# CPU.net
KiCad netlist of a schematic drawn in EAGLE
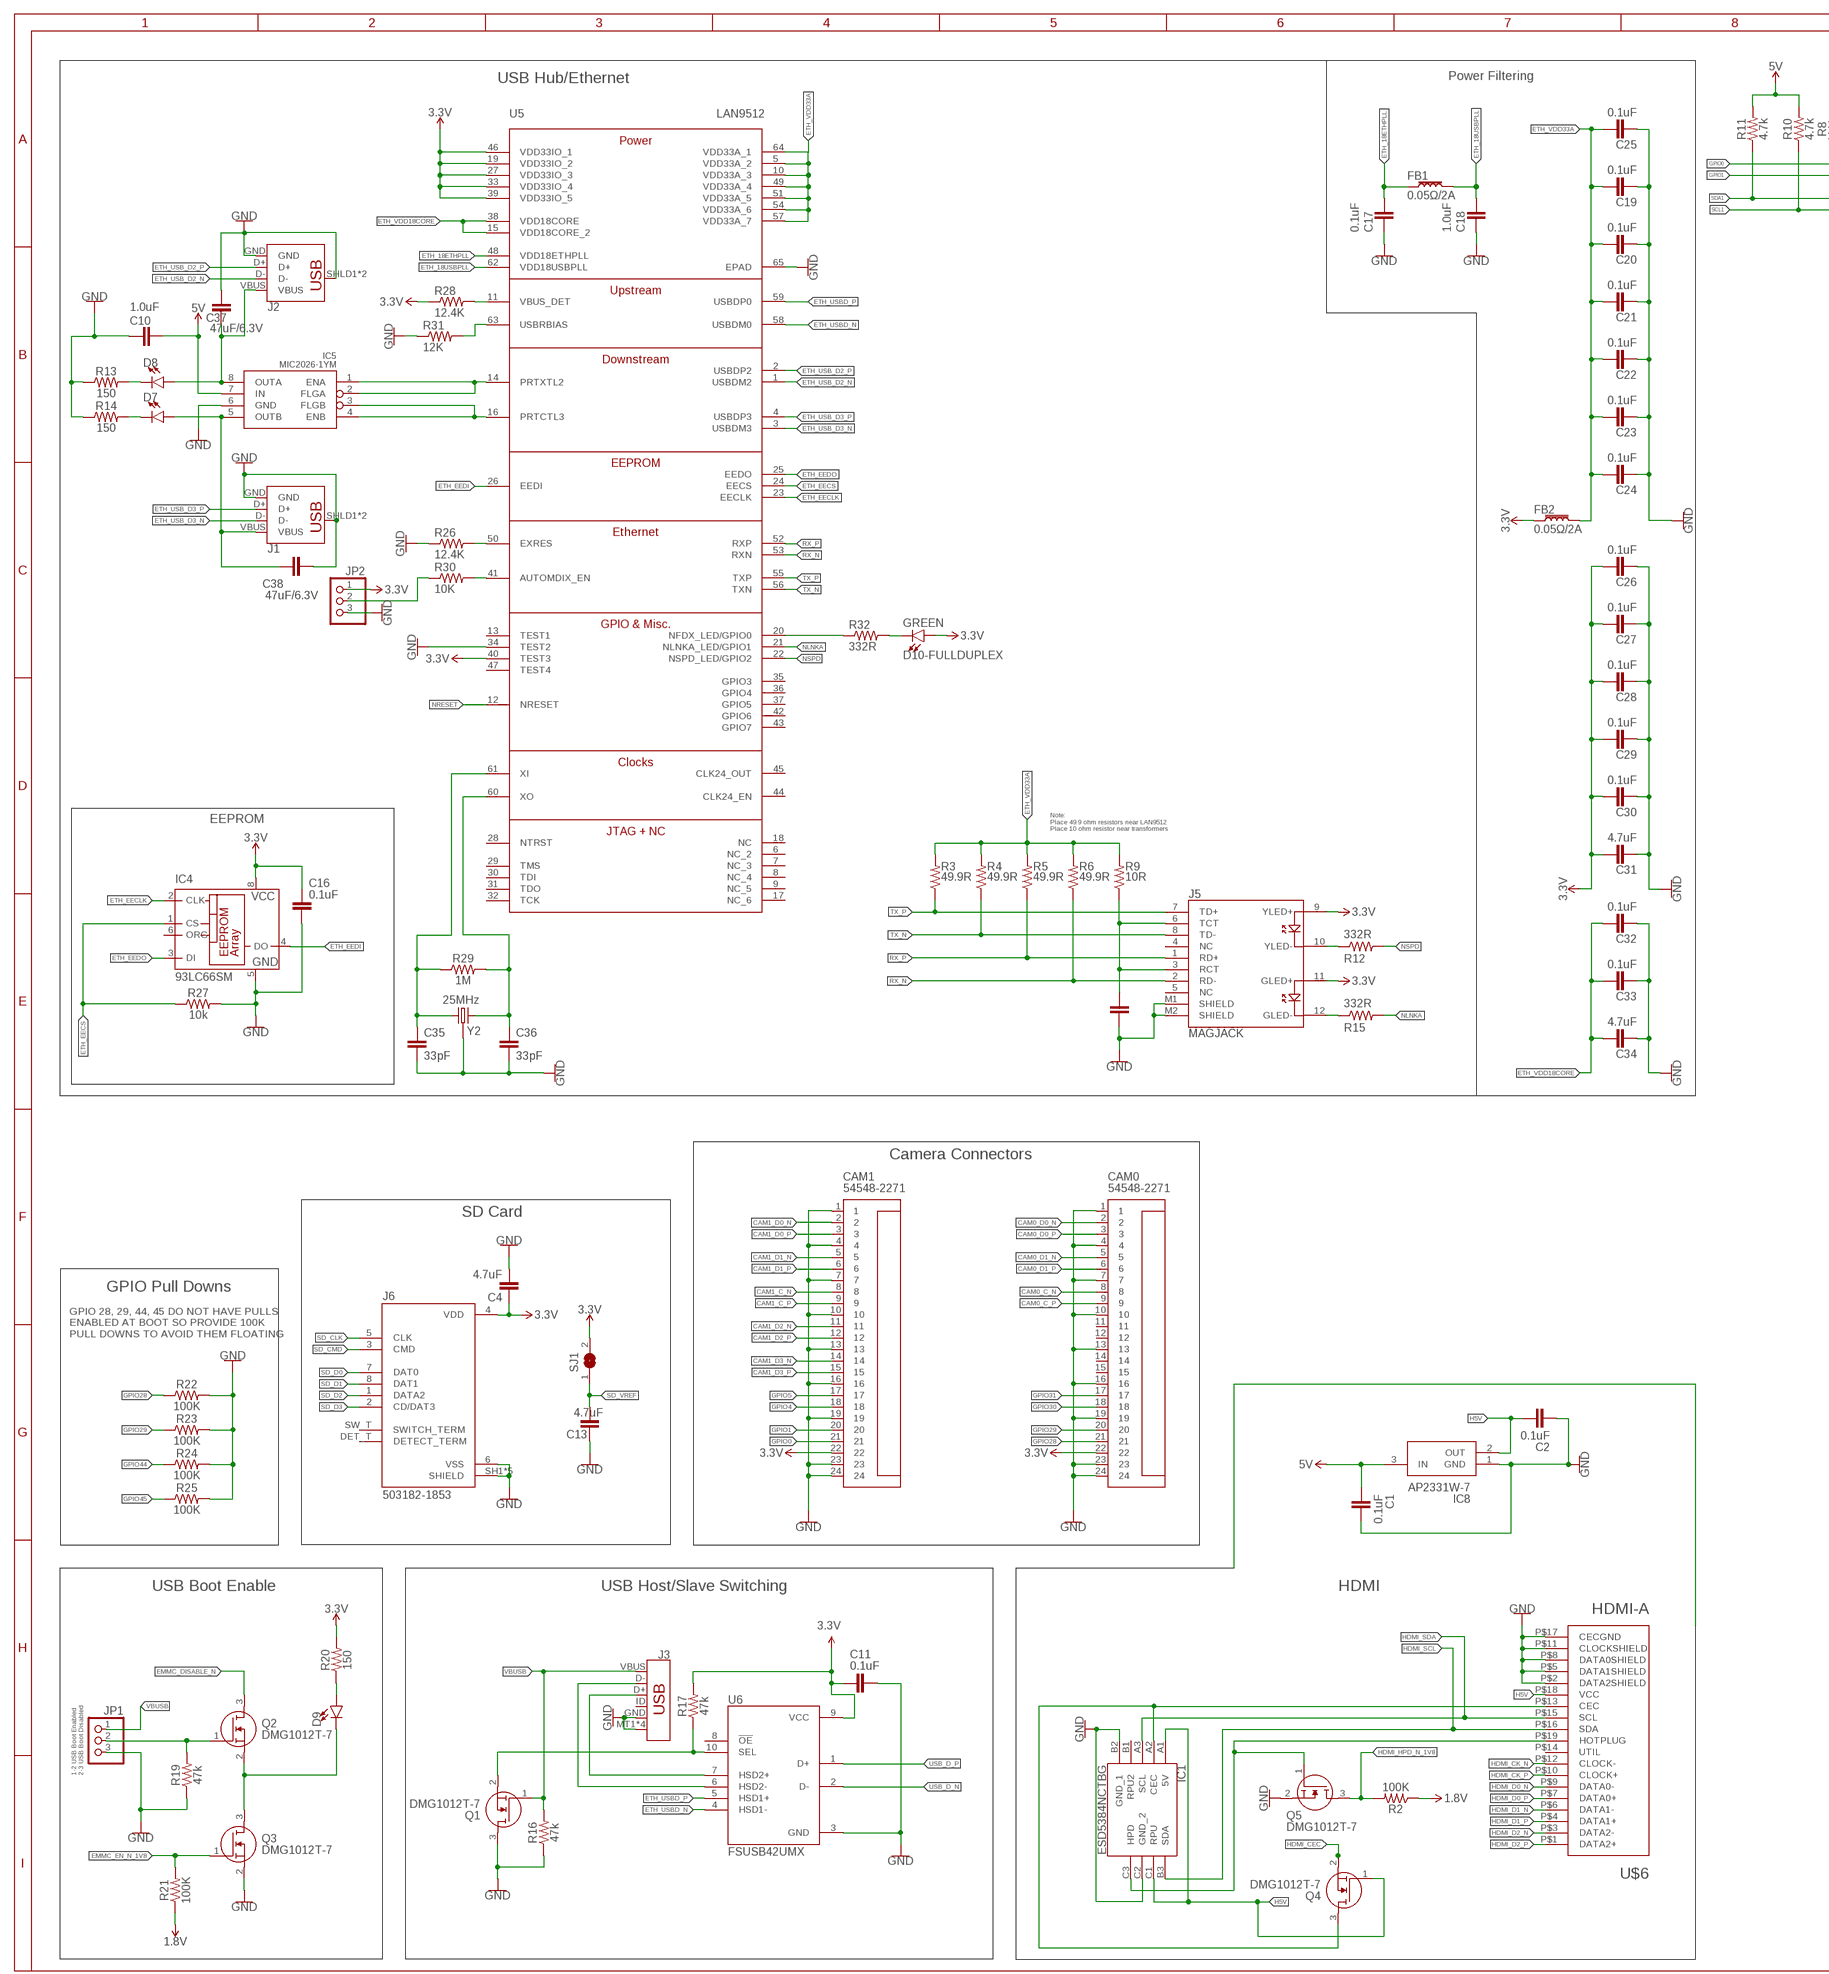
[diagram p0: schematic, sheet 1, part 1 of 2]
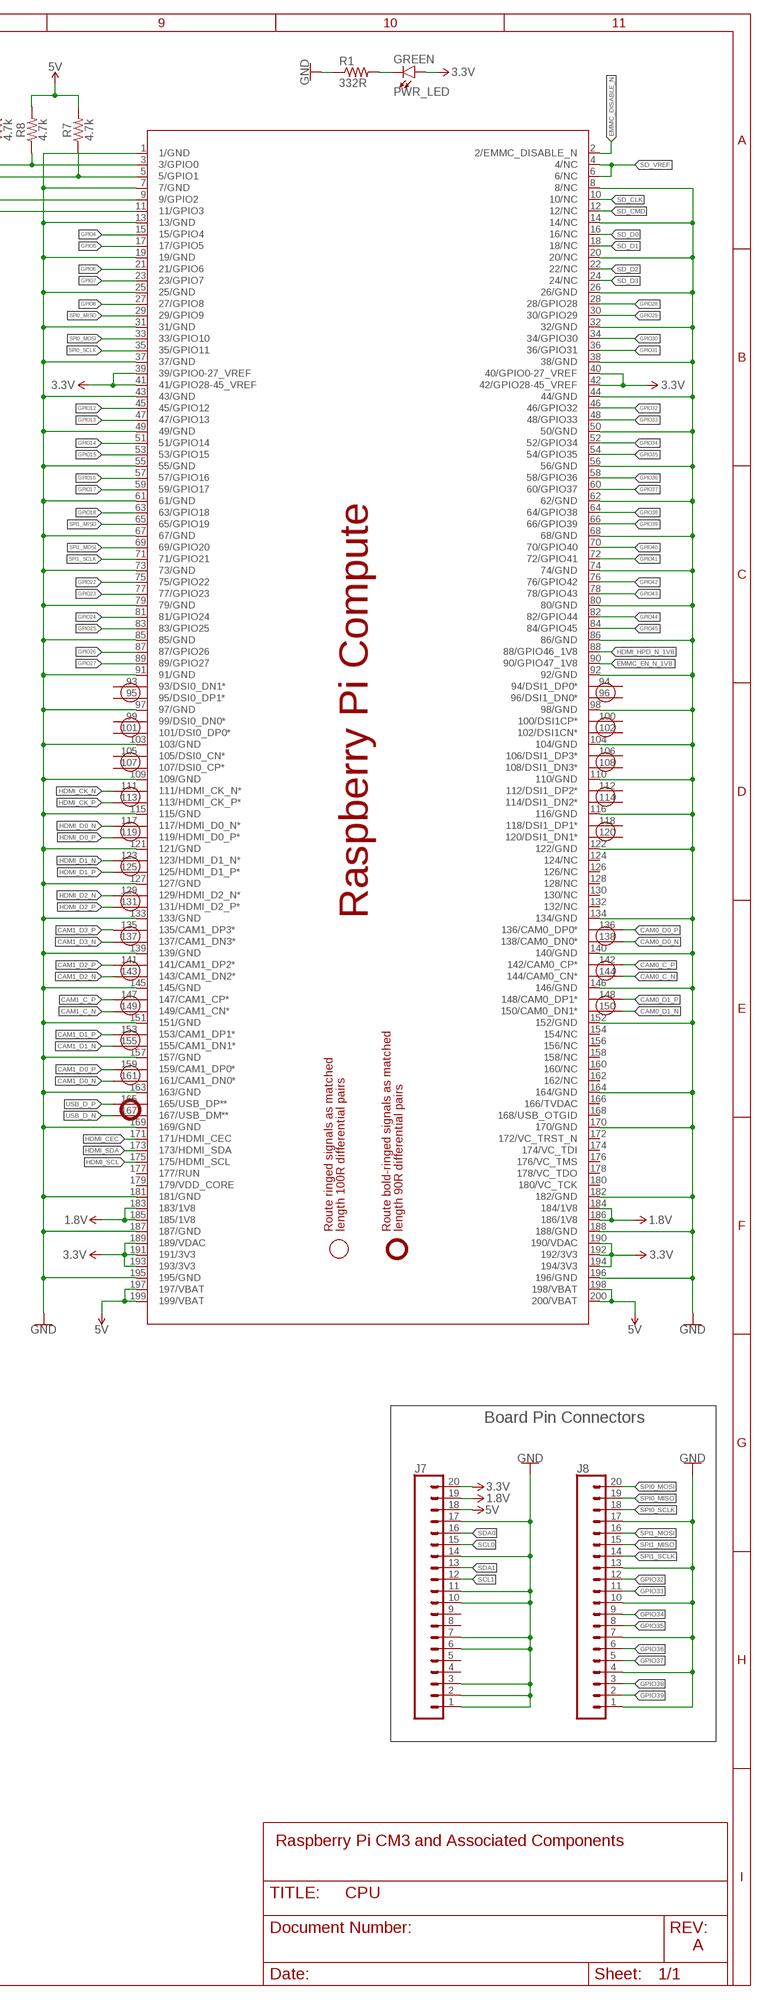
[diagram p1: schematic, sheet 1, part 2 of 2]

(export (version "E")
  (design (tool "Eeschema 10.0.6"))
  (components
    (comp (ref "C1")
      (value "0.1uF")
      (footprint "eagle-import:0402")
      (libsource (lib "eagle-import") (part "0.1UF-0402-16V-10%"))
    )
    (comp (ref "C2")
      (value "0.1uF")
      (footprint "eagle-import:0402")
      (libsource (lib "eagle-import") (part "0.1UF-0402-16V-10%"))
    )
    (comp (ref "C3")
      (value "0.022uF/50V")
      (footprint "eagle-import:0805")
      (libsource (lib "eagle-import") (part "47UF"))
    )
    (comp (ref "C4")
      (value "4.7uF")
      (footprint "eagle-import:0603")
      (libsource (lib "eagle-import") (part "4.7UF-0603-6.3V-(10%)"))
    )
    (comp (ref "C10")
      (value "1.0uF")
      (footprint "eagle-import:0402")
      (libsource (lib "eagle-import") (part "1.0UF-0402-16V-10%"))
    )
    (comp (ref "C11")
      (value "0.1uF")
      (footprint "eagle-import:0402")
      (libsource (lib "eagle-import") (part "0.1UF-0402-16V-10%"))
    )
    (comp (ref "C13")
      (value "4.7uF")
      (footprint "eagle-import:0603")
      (libsource (lib "eagle-import") (part "4.7UF-0603-6.3V-(10%)"))
    )
    (comp (ref "C16")
      (value "0.1uF")
      (footprint "eagle-import:0402")
      (libsource (lib "eagle-import") (part "0.1UF-0402-16V-10%"))
    )
    (comp (ref "C17")
      (value "0.1uF")
      (footprint "eagle-import:0402")
      (libsource (lib "eagle-import") (part "1.0UF-0402-16V-10%"))
    )
    (comp (ref "C18")
      (value "1.0uF")
      (footprint "eagle-import:0402")
      (libsource (lib "eagle-import") (part "1.0UF-0402-16V-10%"))
    )
    (comp (ref "C19")
      (value "0.1uF")
      (footprint "eagle-import:0402")
      (libsource (lib "eagle-import") (part "1.0UF-0402-16V-10%"))
    )
    (comp (ref "C20")
      (value "0.1uF")
      (footprint "eagle-import:0402")
      (libsource (lib "eagle-import") (part "1.0UF-0402-16V-10%"))
    )
    (comp (ref "C21")
      (value "0.1uF")
      (footprint "eagle-import:0402")
      (libsource (lib "eagle-import") (part "1.0UF-0402-16V-10%"))
    )
    (comp (ref "C22")
      (value "0.1uF")
      (footprint "eagle-import:0402")
      (libsource (lib "eagle-import") (part "1.0UF-0402-16V-10%"))
    )
    (comp (ref "C23")
      (value "0.1uF")
      (footprint "eagle-import:0402")
      (libsource (lib "eagle-import") (part "1.0UF-0402-16V-10%"))
    )
    (comp (ref "C24")
      (value "0.1uF")
      (footprint "eagle-import:0402")
      (libsource (lib "eagle-import") (part "1.0UF-0402-16V-10%"))
    )
    (comp (ref "C25")
      (value "0.1uF")
      (footprint "eagle-import:0402")
      (libsource (lib "eagle-import") (part "1.0UF-0402-16V-10%"))
    )
    (comp (ref "C26")
      (value "0.1uF")
      (footprint "eagle-import:0402")
      (libsource (lib "eagle-import") (part "1.0UF-0402-16V-10%"))
    )
    (comp (ref "C27")
      (value "0.1uF")
      (footprint "eagle-import:0402")
      (libsource (lib "eagle-import") (part "1.0UF-0402-16V-10%"))
    )
    (comp (ref "C28")
      (value "0.1uF")
      (footprint "eagle-import:0402")
      (libsource (lib "eagle-import") (part "1.0UF-0402-16V-10%"))
    )
    (comp (ref "C29")
      (value "0.1uF")
      (footprint "eagle-import:0402")
      (libsource (lib "eagle-import") (part "1.0UF-0402-16V-10%"))
    )
    (comp (ref "C30")
      (value "0.1uF")
      (footprint "eagle-import:0402")
      (libsource (lib "eagle-import") (part "1.0UF-0402-16V-10%"))
    )
    (comp (ref "C31")
      (value "4.7uF")
      (footprint "eagle-import:0402")
      (libsource (lib "eagle-import") (part "1.0UF-0402-16V-10%"))
    )
    (comp (ref "C32")
      (value "0.1uF")
      (footprint "eagle-import:0402")
      (libsource (lib "eagle-import") (part "1.0UF-0402-16V-10%"))
    )
    (comp (ref "C33")
      (value "0.1uF")
      (footprint "eagle-import:0402")
      (libsource (lib "eagle-import") (part "1.0UF-0402-16V-10%"))
    )
    (comp (ref "C34")
      (value "4.7uF")
      (footprint "eagle-import:0402")
      (libsource (lib "eagle-import") (part "1.0UF-0402-16V-10%"))
    )
    (comp (ref "C35")
      (value "33pF")
      (footprint "eagle-import:0603")
      (libsource (lib "eagle-import") (part "33PF-0603-50V-5%"))
    )
    (comp (ref "C36")
      (value "33pF")
      (footprint "eagle-import:0603")
      (libsource (lib "eagle-import") (part "33PF-0603-50V-5%"))
    )
    (comp (ref "C37")
      (value "47uF/6.3V")
      (footprint "eagle-import:0805")
      (libsource (lib "eagle-import") (part "47UF"))
    )
    (comp (ref "C38")
      (value "47uF/6.3V")
      (footprint "eagle-import:0805")
      (libsource (lib "eagle-import") (part "47UF"))
    )
    (comp (ref "CAM0")
      (value "54548-2271")
      (footprint "eagle-import:545482271")
      (fields (field (name "MOUSER_PART_NUMBER") "538-54548-2271"))
      (libsource (lib "eagle-import") (part "54548-2271"))
    )
    (comp (ref "CAM1")
      (value "54548-2271")
      (footprint "eagle-import:545482271")
      (fields (field (name "MOUSER_PART_NUMBER") "538-54548-2271"))
      (libsource (lib "eagle-import") (part "54548-2271"))
    )
    (comp (ref "CPU1")
      (value "RPI_COMPUTE")
      (footprint "eagle-import:RPI_COMPUTE")
      (libsource (lib "eagle-import") (part "RPI_COMPUTE"))
    )
    (comp (ref "D7")
      (value "GREEN")
      (footprint "eagle-import:LED-0603")
      (libsource (lib "eagle-import") (part "LED-GREEN0603"))
    )
    (comp (ref "D8")
      (value "GREEN")
      (footprint "eagle-import:LED-0603")
      (libsource (lib "eagle-import") (part "LED-GREEN0603"))
    )
    (comp (ref "D9")
      (value "GREEN")
      (footprint "eagle-import:LED-0603")
      (libsource (lib "eagle-import") (part "LED-GREEN0603"))
    )
    (comp (ref "D10-FULLDUPLEX")
      (value "GREEN")
      (footprint "eagle-import:LED-0603")
      (libsource (lib "eagle-import") (part "LED-GREEN0603"))
    )
    (comp (ref "FB1")
      (value "0.05Ω/2A")
      (footprint "eagle-import:0603")
      (libsource (lib "eagle-import") (part "FERRITE_BEAD-0603"))
    )
    (comp (ref "FB2")
      (value "0.05Ω/2A")
      (footprint "eagle-import:0603")
      (libsource (lib "eagle-import") (part "FERRITE_BEAD-0603"))
    )
    (comp (ref "IC1")
      (value "ESD5384NCTBG")
      (footprint "eagle-import:BGA9C40P3X3_114X114X63")
      (fields (field (name "MOUSER_PART_NUMBER") "863-ESD5384NCTBG"))
      (libsource (lib "eagle-import") (part "ESD5384NCTBG"))
    )
    (comp (ref "IC4")
      (value "93LC66SM")
      (footprint "eagle-import:SO-08M")
      (fields (field (name "MF") "MICROCHIP") (field (name "MPN") "93LC66/SN"))
      (libsource (lib "eagle-import") (part "93SMLC66"))
    )
    (comp (ref "IC5")
      (value "MIC2026-1YM")
      (footprint "eagle-import:SO08")
      (libsource (lib "eagle-import") (part "MIC2026-1YM"))
    )
    (comp (ref "IC8")
      (value "AP2331W-7")
      (footprint "eagle-import:SOT95P285X130-3N")
      (fields (field (name "MOUSER_PART_NUMBER") "621-AP2331W-7"))
      (libsource (lib "eagle-import") (part "AP2331W-7"))
    )
    (comp (ref "J1")
      (value "USB_A_SMT_FEMALE")
      (footprint "eagle-import:USB-A-S-SILK-FEMALE")
      (libsource (lib "eagle-import") (part "USB_A_SMT_FEMALE"))
    )
    (comp (ref "J2")
      (value "USB_A_SMT_FEMALE")
      (footprint "eagle-import:USB-A-S-SILK-FEMALE")
      (libsource (lib "eagle-import") (part "USB_A_SMT_FEMALE"))
    )
    (comp (ref "J3")
      (value "USB_MICRO-B_SMT")
      (footprint "eagle-import:USB-MICROB")
      (libsource (lib "eagle-import") (part "USB_MICRO-B_SMT"))
    )
    (comp (ref "J5")
      (value "MAGJACK")
      (footprint "eagle-import:MAGJACK")
      (libsource (lib "eagle-import") (part "MAGJACK"))
    )
    (comp (ref "J6")
      (value "503182-1853")
      (footprint "eagle-import:MOLEX_503182-1853")
      (fields
        (field (name "DIGI-KEY_PART_NUMBER") "WM9750CT-ND")
        (field (name "MF") "Molex")
        (field (name "MP") "5031821853")
      )
      (libsource (lib "eagle-import") (part "503182-1853"))
    )
    (comp (ref "J7")
      (value "CONN_20")
      (footprint "eagle-import:1X20")
      (libsource (lib "eagle-import") (part "CONN_20"))
    )
    (comp (ref "J8")
      (value "CONN_20")
      (footprint "eagle-import:1X20")
      (libsource (lib "eagle-import") (part "CONN_20"))
    )
    (comp (ref "JP1")
      (value "PINHD-1X3")
      (footprint "eagle-import:1X03")
      (libsource (lib "eagle-import") (part "PINHD-1X3"))
    )
    (comp (ref "JP2")
      (value "PINHD-1X3")
      (footprint "eagle-import:1X03")
      (libsource (lib "eagle-import") (part "PINHD-1X3"))
    )
    (comp (ref "PWR_LED")
      (value "GREEN")
      (footprint "eagle-import:LED-0603")
      (libsource (lib "eagle-import") (part "LED-GREEN0603"))
    )
    (comp (ref "Q1")
      (value "DMG1012T-7")
      (footprint "eagle-import:SOT50P160X80-3N")
      (fields (field (name "MOUSER_PART_NUMBER") "621-DMG1012T-7"))
      (libsource (lib "eagle-import") (part "DMG1012T-7"))
    )
    (comp (ref "Q2")
      (value "DMG1012T-7")
      (footprint "eagle-import:SOT50P160X80-3N")
      (fields (field (name "MOUSER_PART_NUMBER") "621-DMG1012T-7"))
      (libsource (lib "eagle-import") (part "DMG1012T-7"))
    )
    (comp (ref "Q3")
      (value "DMG1012T-7")
      (footprint "eagle-import:SOT50P160X80-3N")
      (fields (field (name "MOUSER_PART_NUMBER") "621-DMG1012T-7"))
      (libsource (lib "eagle-import") (part "DMG1012T-7"))
    )
    (comp (ref "Q4")
      (value "DMG1012T-7")
      (footprint "eagle-import:SOT50P160X80-3N")
      (fields (field (name "MOUSER_PART_NUMBER") "621-DMG1012T-7"))
      (libsource (lib "eagle-import") (part "DMG1012T-7"))
    )
    (comp (ref "Q5")
      (value "DMG1012T-7")
      (footprint "eagle-import:SOT50P160X80-3N")
      (fields (field (name "MOUSER_PART_NUMBER") "621-DMG1012T-7"))
      (libsource (lib "eagle-import") (part "DMG1012T-7"))
    )
    (comp (ref "R1")
      (value "332R")
      (footprint "eagle-import:R0603")
      (libsource (lib "eagle-import") (part "R-US_R0603"))
    )
    (comp (ref "R2")
      (value "100K")
      (footprint "eagle-import:0402")
      (libsource (lib "eagle-import") (part "SparkFun-Resistors_532_100KOHM-0402-1/16W-1%"))
    )
    (comp (ref "R3")
      (value "49.9R")
      (footprint "eagle-import:R0603")
      (libsource (lib "eagle-import") (part "R-US_R0603"))
    )
    (comp (ref "R4")
      (value "49.9R")
      (footprint "eagle-import:R0603")
      (libsource (lib "eagle-import") (part "R-US_R0603"))
    )
    (comp (ref "R5")
      (value "49.9R")
      (footprint "eagle-import:R0603")
      (libsource (lib "eagle-import") (part "R-US_R0603"))
    )
    (comp (ref "R6")
      (value "49.9R")
      (footprint "eagle-import:R0603")
      (libsource (lib "eagle-import") (part "R-US_R0603"))
    )
    (comp (ref "R7")
      (value "4.7k")
      (footprint "eagle-import:0603")
      (libsource (lib "eagle-import") (part "4.7KOHM-0603-1/10W-1%"))
    )
    (comp (ref "R8")
      (value "4.7k")
      (footprint "eagle-import:0603")
      (libsource (lib "eagle-import") (part "4.7KOHM-0603-1/10W-1%"))
    )
    (comp (ref "R9")
      (value "10R")
      (footprint "eagle-import:R0603")
      (libsource (lib "eagle-import") (part "R-US_R0603"))
    )
    (comp (ref "R10")
      (value "4.7k")
      (footprint "eagle-import:0603")
      (libsource (lib "eagle-import") (part "4.7KOHM-0603-1/10W-1%"))
    )
    (comp (ref "R11")
      (value "4.7k")
      (footprint "eagle-import:0603")
      (libsource (lib "eagle-import") (part "4.7KOHM-0603-1/10W-1%"))
    )
    (comp (ref "R12")
      (value "332R")
      (footprint "eagle-import:R0603")
      (libsource (lib "eagle-import") (part "R-US_R0603"))
    )
    (comp (ref "R13")
      (value "150")
      (footprint "eagle-import:0603")
      (libsource (lib "eagle-import") (part "150OHM-0603-1/10W-1%"))
    )
    (comp (ref "R14")
      (value "150")
      (footprint "eagle-import:0603")
      (libsource (lib "eagle-import") (part "150OHM-0603-1/10W-1%"))
    )
    (comp (ref "R15")
      (value "332R")
      (footprint "eagle-import:R0603")
      (libsource (lib "eagle-import") (part "R-US_R0603"))
    )
    (comp (ref "R16")
      (value "47k")
      (footprint "eagle-import:0603")
      (libsource (lib "eagle-import") (part "47KOHM-0603-1/10W-1%"))
    )
    (comp (ref "R17")
      (value "47k")
      (footprint "eagle-import:0603")
      (libsource (lib "eagle-import") (part "47KOHM-0603-1/10W-1%"))
    )
    (comp (ref "R19")
      (value "47k")
      (footprint "eagle-import:0603")
      (libsource (lib "eagle-import") (part "47KOHM-0603-1/10W-1%"))
    )
    (comp (ref "R20")
      (value "150")
      (footprint "eagle-import:0603")
      (libsource (lib "eagle-import") (part "150OHM-0603-1/10W-1%"))
    )
    (comp (ref "R21")
      (value "100K")
      (footprint "eagle-import:0402")
      (libsource (lib "eagle-import") (part "100KOHM-0402-1/16W-1%"))
    )
    (comp (ref "R22")
      (value "100K")
      (footprint "eagle-import:0402")
      (libsource (lib "eagle-import") (part "100KOHM-0402-1/16W-1%"))
    )
    (comp (ref "R23")
      (value "100K")
      (footprint "eagle-import:0402")
      (libsource (lib "eagle-import") (part "100KOHM-0402-1/16W-1%"))
    )
    (comp (ref "R24")
      (value "100K")
      (footprint "eagle-import:0402")
      (libsource (lib "eagle-import") (part "100KOHM-0402-1/16W-1%"))
    )
    (comp (ref "R25")
      (value "100K")
      (footprint "eagle-import:0402")
      (libsource (lib "eagle-import") (part "100KOHM-0402-1/16W-1%"))
    )
    (comp (ref "R26")
      (value "12.4K")
      (footprint "eagle-import:R0603")
      (libsource (lib "eagle-import") (part "R-US_R0603"))
    )
    (comp (ref "R27")
      (value "10k")
      (footprint "eagle-import:0603")
      (libsource (lib "eagle-import") (part "10KOHM-0603-1/10W-1%"))
    )
    (comp (ref "R28")
      (value "12.4K")
      (footprint "eagle-import:R0603")
      (libsource (lib "eagle-import") (part "R-US_R0603"))
    )
    (comp (ref "R29")
      (value "1M")
      (footprint "eagle-import:0603")
      (libsource (lib "eagle-import") (part "1MOHM-0603-1/4W-5%"))
    )
    (comp (ref "R30")
      (value "10K")
      (footprint "eagle-import:R0603")
      (libsource (lib "eagle-import") (part "R-US_R0603"))
    )
    (comp (ref "R31")
      (value "12K")
      (footprint "eagle-import:R0603")
      (libsource (lib "eagle-import") (part "R-US_R0603"))
    )
    (comp (ref "R32")
      (value "332R")
      (footprint "eagle-import:R0603")
      (libsource (lib "eagle-import") (part "R-US_R0603"))
    )
    (comp (ref "SJ1") (value "SJ") (footprint "eagle-import:SJ") (libsource (lib "eagle-import") (part "SJ")))
    (comp (ref "U$6")
      (value "HDMI-A")
      (footprint "eagle-import:HDMI_A")
      (libsource (lib "eagle-import") (part "HDMI-A"))
    )
    (comp (ref "U5")
      (value "LAN9512-JZX")
      (footprint "eagle-import:QFN64_9X9MC")
      (fields (field (name "MANUFACTURER_PART_NUMBER") "LAN9512JZX"))
      (libsource (lib "eagle-import") (part "LAN9512-JZX"))
    )
    (comp (ref "U6")
      (value "FSUSB42UMX")
      (footprint "eagle-import:IC_FSUSB42UMX")
      (fields (field (name "DIGI-KEY_PART_NUMBER") "FSUSB42UMXCT-ND") (field (name "MF") "ON Semiconductor"))
      (libsource (lib "eagle-import") (part "FSUSB42UMX"))
    )
    (comp (ref "Y2")
      (value "25MHz")
      (footprint "eagle-import:CRYSTAL-SMD-3.2X2.5MM")
      (libsource (lib "eagle-import") (part "CRYSTAL-GROUNDEDSMD-3.2X2.5"))
    )
  )
  (nets
    (net (code "1") (name "1.8V") (class "Default")
      (node (ref "CPU1") (pin "183") (pinfunction "183/1V8_183") (pintype "bidirectional"))
      (node (ref "CPU1") (pin "184") (pinfunction "184/1V8_184") (pintype "bidirectional"))
      (node (ref "CPU1") (pin "185") (pinfunction "185/1V8_185") (pintype "bidirectional"))
      (node (ref "CPU1") (pin "186") (pinfunction "186/1V8_186") (pintype "bidirectional"))
      (node (ref "J7") (pin "19") (pinfunction "19_19") (pintype "passive"))
      (node (ref "R2") (pin "1") (pinfunction "1_1") (pintype "passive"))
      (node (ref "R21") (pin "1") (pinfunction "1_1") (pintype "passive"))
    )
    (net (code "2") (name "3.3V") (class "Default")
      (node (ref "C11") (pin "2") (pinfunction "2_2") (pintype "passive"))
      (node (ref "C16") (pin "1") (pinfunction "1_1") (pintype "passive"))
      (node (ref "C26") (pin "2") (pinfunction "2_2") (pintype "passive"))
      (node (ref "C27") (pin "2") (pinfunction "2_2") (pintype "passive"))
      (node (ref "C28") (pin "2") (pinfunction "2_2") (pintype "passive"))
      (node (ref "C29") (pin "2") (pinfunction "2_2") (pintype "passive"))
      (node (ref "C30") (pin "2") (pinfunction "2_2") (pintype "passive"))
      (node (ref "C31") (pin "2") (pinfunction "2_2") (pintype "passive"))
      (node (ref "C4") (pin "1") (pinfunction "1_1") (pintype "passive"))
      (node (ref "CAM0") (pin "22") (pinfunction "22_22") (pintype "bidirectional"))
      (node (ref "CAM1") (pin "22") (pinfunction "22_22") (pintype "bidirectional"))
      (node (ref "CPU1") (pin "189") (pinfunction "189/VDAC_189") (pintype "bidirectional"))
      (node (ref "CPU1") (pin "190") (pinfunction "190/VDAC_190") (pintype "bidirectional"))
      (node (ref "CPU1") (pin "191") (pinfunction "191/3V3_191") (pintype "bidirectional"))
      (node (ref "CPU1") (pin "192") (pinfunction "192/3V3_192") (pintype "bidirectional"))
      (node (ref "CPU1") (pin "193") (pinfunction "193/3V3_193") (pintype "bidirectional"))
      (node (ref "CPU1") (pin "194") (pinfunction "194/3V3_194") (pintype "bidirectional"))
      (node (ref "CPU1") (pin "39") (pinfunction "39/GPIO0-27_VREF_39") (pintype "bidirectional"))
      (node (ref "CPU1") (pin "40") (pinfunction "40/GPIO0-27_VREF_40") (pintype "bidirectional"))
      (node (ref "CPU1") (pin "41") (pinfunction "41/GPIO28-45_VREF_41") (pintype "bidirectional"))
      (node (ref "CPU1") (pin "42") (pinfunction "42/GPIO28-45_VREF_42") (pintype "bidirectional"))
      (node (ref "D10-FULLDUPLEX") (pin "A") (pinfunction "A_A") (pintype "passive"))
      (node (ref "FB2") (pin "1") (pinfunction "1_1") (pintype "passive"))
      (node (ref "IC4") (pin "8") (pinfunction "VCC_8") (pintype "power_in"))
      (node (ref "J5") (pin "11") (pinfunction "GLED+_11") (pintype "bidirectional"))
      (node (ref "J5") (pin "9") (pinfunction "YLED+_9") (pintype "bidirectional"))
      (node (ref "J6") (pin "4") (pinfunction "VDD_4") (pintype "passive"))
      (node (ref "J7") (pin "20") (pinfunction "20_20") (pintype "passive"))
      (node (ref "JP2") (pin "1") (pinfunction "1_1") (pintype "passive"))
      (node (ref "PWR_LED") (pin "A") (pinfunction "A_A") (pintype "passive"))
      (node (ref "R17") (pin "2") (pinfunction "2_2") (pintype "passive"))
      (node (ref "R20") (pin "2") (pinfunction "2_2") (pintype "passive"))
      (node (ref "R28") (pin "1") (pinfunction "1_1") (pintype "passive"))
      (node (ref "SJ1") (pin "2") (pinfunction "2_2") (pintype "passive"))
      (node (ref "U5") (pin "19") (pinfunction "VDD33IO_2_19") (pintype "power_in"))
      (node (ref "U5") (pin "27") (pinfunction "VDD33IO_3_27") (pintype "power_in"))
      (node (ref "U5") (pin "33") (pinfunction "VDD33IO_4_33") (pintype "power_in"))
      (node (ref "U5") (pin "39") (pinfunction "VDD33IO_5_39") (pintype "power_in"))
      (node (ref "U5") (pin "40") (pinfunction "TEST3_40") (pintype "passive"))
      (node (ref "U5") (pin "46") (pinfunction "VDD33IO_1_46") (pintype "power_in"))
      (node (ref "U6") (pin "9") (pinfunction "VCC_9") (pintype "power_in"))
    )
    (net (code "3") (name "5V") (class "Default")
      (node (ref "C1") (pin "2") (pinfunction "2_2") (pintype "passive"))
      (node (ref "C10") (pin "2") (pinfunction "2_2") (pintype "passive"))
      (node (ref "CPU1") (pin "197") (pinfunction "197/VBAT_197") (pintype "bidirectional"))
      (node (ref "CPU1") (pin "198") (pinfunction "198/VBAT_198") (pintype "bidirectional"))
      (node (ref "CPU1") (pin "199") (pinfunction "199/VBAT_199") (pintype "bidirectional"))
      (node (ref "CPU1") (pin "200") (pinfunction "200/VBAT_200") (pintype "bidirectional"))
      (node (ref "IC5") (pin "7") (pinfunction "IN_7") (pintype "input"))
      (node (ref "IC8") (pin "3") (pinfunction "IN_3") (pintype "bidirectional"))
      (node (ref "J7") (pin "18") (pinfunction "18_18") (pintype "passive"))
      (node (ref "R10") (pin "2") (pinfunction "2_2") (pintype "passive"))
      (node (ref "R11") (pin "2") (pinfunction "2_2") (pintype "passive"))
      (node (ref "R7") (pin "2") (pinfunction "2_2") (pintype "passive"))
      (node (ref "R8") (pin "2") (pinfunction "2_2") (pintype "passive"))
    )
    (net (code "4") (name "CAM0_C_N") (class "Default")
      (node (ref "CAM0") (pin "8") (pinfunction "8_8") (pintype "bidirectional"))
      (node (ref "CPU1") (pin "144") (pinfunction "144/CAM0_CN*_144") (pintype "bidirectional"))
    )
    (net (code "5") (name "CAM0_C_P") (class "Default")
      (node (ref "CAM0") (pin "9") (pinfunction "9_9") (pintype "bidirectional"))
      (node (ref "CPU1") (pin "142") (pinfunction "142/CAM0_CP*_142") (pintype "bidirectional"))
    )
    (net (code "6") (name "CAM0_D0_N") (class "Default")
      (node (ref "CAM0") (pin "2") (pinfunction "2_2") (pintype "bidirectional"))
      (node (ref "CPU1") (pin "138") (pinfunction "138/CAM0_DN0*_138") (pintype "bidirectional"))
    )
    (net (code "7") (name "CAM0_D0_P") (class "Default")
      (node (ref "CAM0") (pin "3") (pinfunction "3_3") (pintype "bidirectional"))
      (node (ref "CPU1") (pin "136") (pinfunction "136/CAM0_DP0*_136") (pintype "bidirectional"))
    )
    (net (code "8") (name "CAM0_D1_N") (class "Default")
      (node (ref "CAM0") (pin "5") (pinfunction "5_5") (pintype "bidirectional"))
      (node (ref "CPU1") (pin "150") (pinfunction "150/CAM0_DN1*_150") (pintype "bidirectional"))
    )
    (net (code "9") (name "CAM0_D1_P") (class "Default")
      (node (ref "CAM0") (pin "6") (pinfunction "6_6") (pintype "bidirectional"))
      (node (ref "CPU1") (pin "148") (pinfunction "148/CAM0_DP1*_148") (pintype "bidirectional"))
    )
    (net (code "10") (name "CAM1_C_N") (class "Default")
      (node (ref "CAM1") (pin "8") (pinfunction "8_8") (pintype "bidirectional"))
      (node (ref "CPU1") (pin "149") (pinfunction "149/CAM1_CN*_149") (pintype "bidirectional"))
    )
    (net (code "11") (name "CAM1_C_P") (class "Default")
      (node (ref "CAM1") (pin "9") (pinfunction "9_9") (pintype "bidirectional"))
      (node (ref "CPU1") (pin "147") (pinfunction "147/CAM1_CP*_147") (pintype "bidirectional"))
    )
    (net (code "12") (name "CAM1_D0_N") (class "Default")
      (node (ref "CAM1") (pin "2") (pinfunction "2_2") (pintype "bidirectional"))
      (node (ref "CPU1") (pin "161") (pinfunction "161/CAM1_DN0*_161") (pintype "bidirectional"))
    )
    (net (code "13") (name "CAM1_D0_P") (class "Default")
      (node (ref "CAM1") (pin "3") (pinfunction "3_3") (pintype "bidirectional"))
      (node (ref "CPU1") (pin "159") (pinfunction "159/CAM1_DP0*_159") (pintype "bidirectional"))
    )
    (net (code "14") (name "CAM1_D1_N") (class "Default")
      (node (ref "CAM1") (pin "5") (pinfunction "5_5") (pintype "bidirectional"))
      (node (ref "CPU1") (pin "155") (pinfunction "155/CAM1_DN1*_155") (pintype "bidirectional"))
    )
    (net (code "15") (name "CAM1_D1_P") (class "Default")
      (node (ref "CAM1") (pin "6") (pinfunction "6_6") (pintype "bidirectional"))
      (node (ref "CPU1") (pin "153") (pinfunction "153/CAM1_DP1*_153") (pintype "bidirectional"))
    )
    (net (code "16") (name "CAM1_D2_N") (class "Default")
      (node (ref "CAM1") (pin "11") (pinfunction "11_11") (pintype "bidirectional"))
      (node (ref "CPU1") (pin "143") (pinfunction "143/CAM1_DN2*_143") (pintype "bidirectional"))
    )
    (net (code "17") (name "CAM1_D2_P") (class "Default")
      (node (ref "CAM1") (pin "12") (pinfunction "12_12") (pintype "bidirectional"))
      (node (ref "CPU1") (pin "141") (pinfunction "141/CAM1_DP2*_141") (pintype "bidirectional"))
    )
    (net (code "18") (name "CAM1_D3_N") (class "Default")
      (node (ref "CAM1") (pin "14") (pinfunction "14_14") (pintype "bidirectional"))
      (node (ref "CPU1") (pin "137") (pinfunction "137/CAM1_DN3*_137") (pintype "bidirectional"))
    )
    (net (code "19") (name "CAM1_D3_P") (class "Default")
      (node (ref "CAM1") (pin "15") (pinfunction "15_15") (pintype "bidirectional"))
      (node (ref "CPU1") (pin "135") (pinfunction "135/CAM1_DP3*_135") (pintype "bidirectional"))
    )
    (net (code "20") (name "EMMC_DISABLE_N") (class "Default")
      (node (ref "CPU1") (pin "2") (pinfunction "2/EMMC_DISABLE_N_2") (pintype "bidirectional"))
      (node (ref "Q2") (pin "3") (pinfunction "D_3") (pintype "bidirectional"))
    )
    (net (code "21") (name "EMMC_EN_N_1V8") (class "Default")
      (node (ref "CPU1") (pin "90") (pinfunction "90/GPIO47_1V8_90") (pintype "bidirectional"))
      (node (ref "Q3") (pin "1") (pinfunction "G_1") (pintype "bidirectional"))
      (node (ref "R21") (pin "2") (pinfunction "2_2") (pintype "passive"))
    )
    (net (code "22") (name "ETH_18ETHPLL") (class "Default")
      (node (ref "C17") (pin "2") (pinfunction "2_2") (pintype "passive"))
      (node (ref "FB1") (pin "1") (pinfunction "1_1") (pintype "passive"))
      (node (ref "U5") (pin "48") (pinfunction "VDD18ETHPLL_48") (pintype "power_in"))
    )
    (net (code "23") (name "ETH_18USBPLL") (class "Default")
      (node (ref "C18") (pin "2") (pinfunction "2_2") (pintype "passive"))
      (node (ref "FB1") (pin "2") (pinfunction "2_2") (pintype "passive"))
      (node (ref "U5") (pin "62") (pinfunction "VDD18USBPLL_62") (pintype "power_in"))
    )
    (net (code "24") (name "ETH_EECLK") (class "Default")
      (node (ref "IC4") (pin "2") (pinfunction "CLK_2") (pintype "input"))
      (node (ref "U5") (pin "23") (pinfunction "EECLK_23") (pintype "output"))
    )
    (net (code "25") (name "ETH_EECS") (class "Default")
      (node (ref "IC4") (pin "1") (pinfunction "CS_1") (pintype "input"))
      (node (ref "R27") (pin "1") (pinfunction "1_1") (pintype "passive"))
      (node (ref "U5") (pin "24") (pinfunction "EECS_24") (pintype "output"))
    )
    (net (code "26") (name "ETH_EEDI") (class "Default")
      (node (ref "IC4") (pin "4") (pinfunction "DO_4") (pintype "tri_state"))
      (node (ref "U5") (pin "26") (pinfunction "EEDI_26") (pintype "input"))
    )
    (net (code "27") (name "ETH_EEDO") (class "Default")
      (node (ref "IC4") (pin "3") (pinfunction "DI_3") (pintype "input"))
      (node (ref "U5") (pin "25") (pinfunction "EEDO_25") (pintype "output"))
    )
    (net (code "28") (name "ETH_USBD_N") (class "Default")
      (node (ref "U5") (pin "58") (pinfunction "USBDM0_58") (pintype "bidirectional"))
      (node (ref "U6") (pin "4") (pinfunction "HSD1-_4") (pintype "input"))
    )
    (net (code "29") (name "ETH_USBD_P") (class "Default")
      (node (ref "U5") (pin "59") (pinfunction "USBDP0_59") (pintype "bidirectional"))
      (node (ref "U6") (pin "5") (pinfunction "HSD1+_5") (pintype "input"))
    )
    (net (code "30") (name "ETH_USB_D2_N") (class "Default")
      (node (ref "J2") (pin "D-") (pinfunction "D-_D-") (pintype "bidirectional"))
      (node (ref "U5") (pin "1") (pinfunction "USBDM2_1") (pintype "bidirectional"))
    )
    (net (code "31") (name "ETH_USB_D2_P") (class "Default")
      (node (ref "J2") (pin "D+") (pinfunction "D+_D+") (pintype "bidirectional"))
      (node (ref "U5") (pin "2") (pinfunction "USBDP2_2") (pintype "bidirectional"))
    )
    (net (code "32") (name "ETH_USB_D3_N") (class "Default")
      (node (ref "J1") (pin "D-") (pinfunction "D-_D-") (pintype "bidirectional"))
      (node (ref "U5") (pin "3") (pinfunction "USBDM3_3") (pintype "bidirectional"))
    )
    (net (code "33") (name "ETH_USB_D3_P") (class "Default")
      (node (ref "J1") (pin "D+") (pinfunction "D+_D+") (pintype "bidirectional"))
      (node (ref "U5") (pin "4") (pinfunction "USBDP3_4") (pintype "bidirectional"))
    )
    (net (code "34") (name "ETH_VDD18CORE") (class "Default")
      (node (ref "C32") (pin "2") (pinfunction "2_2") (pintype "passive"))
      (node (ref "C33") (pin "2") (pinfunction "2_2") (pintype "passive"))
      (node (ref "C34") (pin "2") (pinfunction "2_2") (pintype "passive"))
      (node (ref "U5") (pin "15") (pinfunction "VDD18CORE_2_15") (pintype "power_in"))
      (node (ref "U5") (pin "38") (pinfunction "VDD18CORE_38") (pintype "power_in"))
    )
    (net (code "35") (name "ETH_VDD33A") (class "Default")
      (node (ref "C19") (pin "2") (pinfunction "2_2") (pintype "passive"))
      (node (ref "C20") (pin "2") (pinfunction "2_2") (pintype "passive"))
      (node (ref "C21") (pin "2") (pinfunction "2_2") (pintype "passive"))
      (node (ref "C22") (pin "2") (pinfunction "2_2") (pintype "passive"))
      (node (ref "C23") (pin "2") (pinfunction "2_2") (pintype "passive"))
      (node (ref "C24") (pin "2") (pinfunction "2_2") (pintype "passive"))
      (node (ref "C25") (pin "2") (pinfunction "2_2") (pintype "passive"))
      (node (ref "FB2") (pin "2") (pinfunction "2_2") (pintype "passive"))
      (node (ref "R3") (pin "2") (pinfunction "2_2") (pintype "passive"))
      (node (ref "R4") (pin "2") (pinfunction "2_2") (pintype "passive"))
      (node (ref "R5") (pin "2") (pinfunction "2_2") (pintype "passive"))
      (node (ref "R6") (pin "2") (pinfunction "2_2") (pintype "passive"))
      (node (ref "R9") (pin "2") (pinfunction "2_2") (pintype "passive"))
      (node (ref "U5") (pin "10") (pinfunction "VDD33A_3_10") (pintype "power_in"))
      (node (ref "U5") (pin "49") (pinfunction "VDD33A_4_49") (pintype "power_in"))
      (node (ref "U5") (pin "5") (pinfunction "VDD33A_2_5") (pintype "power_in"))
      (node (ref "U5") (pin "51") (pinfunction "VDD33A_5_51") (pintype "power_in"))
      (node (ref "U5") (pin "54") (pinfunction "VDD33A_6_54") (pintype "power_in"))
      (node (ref "U5") (pin "57") (pinfunction "VDD33A_7_57") (pintype "power_in"))
      (node (ref "U5") (pin "64") (pinfunction "VDD33A_1_64") (pintype "power_in"))
    )
    (net (code "36") (name "GND") (class "Default")
      (node (ref "C1") (pin "1") (pinfunction "1_1") (pintype "passive"))
      (node (ref "C10") (pin "1") (pinfunction "1_1") (pintype "passive"))
      (node (ref "C11") (pin "1") (pinfunction "1_1") (pintype "passive"))
      (node (ref "C13") (pin "1") (pinfunction "1_1") (pintype "passive"))
      (node (ref "C16") (pin "2") (pinfunction "2_2") (pintype "passive"))
      (node (ref "C17") (pin "1") (pinfunction "1_1") (pintype "passive"))
      (node (ref "C18") (pin "1") (pinfunction "1_1") (pintype "passive"))
      (node (ref "C19") (pin "1") (pinfunction "1_1") (pintype "passive"))
      (node (ref "C2") (pin "2") (pinfunction "2_2") (pintype "passive"))
      (node (ref "C20") (pin "1") (pinfunction "1_1") (pintype "passive"))
      (node (ref "C21") (pin "1") (pinfunction "1_1") (pintype "passive"))
      (node (ref "C22") (pin "1") (pinfunction "1_1") (pintype "passive"))
      (node (ref "C23") (pin "1") (pinfunction "1_1") (pintype "passive"))
      (node (ref "C24") (pin "1") (pinfunction "1_1") (pintype "passive"))
      (node (ref "C25") (pin "1") (pinfunction "1_1") (pintype "passive"))
      (node (ref "C26") (pin "1") (pinfunction "1_1") (pintype "passive"))
      (node (ref "C27") (pin "1") (pinfunction "1_1") (pintype "passive"))
      (node (ref "C28") (pin "1") (pinfunction "1_1") (pintype "passive"))
      (node (ref "C29") (pin "1") (pinfunction "1_1") (pintype "passive"))
      (node (ref "C3") (pin "1") (pinfunction "1_1") (pintype "passive"))
      (node (ref "C30") (pin "1") (pinfunction "1_1") (pintype "passive"))
      (node (ref "C31") (pin "1") (pinfunction "1_1") (pintype "passive"))
      (node (ref "C32") (pin "1") (pinfunction "1_1") (pintype "passive"))
      (node (ref "C33") (pin "1") (pinfunction "1_1") (pintype "passive"))
      (node (ref "C34") (pin "1") (pinfunction "1_1") (pintype "passive"))
      (node (ref "C35") (pin "2") (pinfunction "2_2") (pintype "passive"))
      (node (ref "C36") (pin "2") (pinfunction "2_2") (pintype "passive"))
      (node (ref "C37") (pin "2") (pinfunction "2_2") (pintype "passive"))
      (node (ref "C38") (pin "2") (pinfunction "2_2") (pintype "passive"))
      (node (ref "C4") (pin "2") (pinfunction "2_2") (pintype "passive"))
      (node (ref "CAM0") (pin "1") (pinfunction "1_1") (pintype "bidirectional"))
      (node (ref "CAM0") (pin "10") (pinfunction "10_10") (pintype "bidirectional"))
      (node (ref "CAM0") (pin "13") (pinfunction "13_13") (pintype "bidirectional"))
      (node (ref "CAM0") (pin "16") (pinfunction "16_16") (pintype "bidirectional"))
      (node (ref "CAM0") (pin "19") (pinfunction "19_19") (pintype "bidirectional"))
      (node (ref "CAM0") (pin "23") (pinfunction "23_23") (pintype "bidirectional"))
      (node (ref "CAM0") (pin "24") (pinfunction "24_24") (pintype "bidirectional"))
      (node (ref "CAM0") (pin "4") (pinfunction "4_4") (pintype "bidirectional"))
      (node (ref "CAM0") (pin "7") (pinfunction "7_7") (pintype "bidirectional"))
      (node (ref "CAM1") (pin "1") (pinfunction "1_1") (pintype "bidirectional"))
      (node (ref "CAM1") (pin "10") (pinfunction "10_10") (pintype "bidirectional"))
      (node (ref "CAM1") (pin "13") (pinfunction "13_13") (pintype "bidirectional"))
      (node (ref "CAM1") (pin "16") (pinfunction "16_16") (pintype "bidirectional"))
      (node (ref "CAM1") (pin "19") (pinfunction "19_19") (pintype "bidirectional"))
      (node (ref "CAM1") (pin "23") (pinfunction "23_23") (pintype "bidirectional"))
      (node (ref "CAM1") (pin "24") (pinfunction "24_24") (pintype "bidirectional"))
      (node (ref "CAM1") (pin "4") (pinfunction "4_4") (pintype "bidirectional"))
      (node (ref "CAM1") (pin "7") (pinfunction "7_7") (pintype "bidirectional"))
      (node (ref "CPU1") (pin "1") (pinfunction "1/GND_1") (pintype "bidirectional"))
      (node (ref "CPU1") (pin "103") (pinfunction "103/GND_103") (pintype "bidirectional"))
      (node (ref "CPU1") (pin "104") (pinfunction "104/GND_104") (pintype "bidirectional"))
      (node (ref "CPU1") (pin "109") (pinfunction "109/GND_109") (pintype "bidirectional"))
      (node (ref "CPU1") (pin "110") (pinfunction "110/GND_110") (pintype "bidirectional"))
      (node (ref "CPU1") (pin "115") (pinfunction "115/GND_115") (pintype "bidirectional"))
      (node (ref "CPU1") (pin "116") (pinfunction "116/GND_116") (pintype "bidirectional"))
      (node (ref "CPU1") (pin "121") (pinfunction "121/GND_121") (pintype "bidirectional"))
      (node (ref "CPU1") (pin "122") (pinfunction "122/GND_122") (pintype "bidirectional"))
      (node (ref "CPU1") (pin "127") (pinfunction "127/GND_127") (pintype "bidirectional"))
      (node (ref "CPU1") (pin "13") (pinfunction "13/GND_13") (pintype "bidirectional"))
      (node (ref "CPU1") (pin "133") (pinfunction "133/GND_133") (pintype "bidirectional"))
      (node (ref "CPU1") (pin "134") (pinfunction "134/GND_134") (pintype "bidirectional"))
      (node (ref "CPU1") (pin "139") (pinfunction "139/GND_139") (pintype "bidirectional"))
      (node (ref "CPU1") (pin "14") (pinfunction "14/NC_14") (pintype "bidirectional"))
      (node (ref "CPU1") (pin "140") (pinfunction "140/GND_140") (pintype "bidirectional"))
      (node (ref "CPU1") (pin "145") (pinfunction "145/GND_145") (pintype "bidirectional"))
      (node (ref "CPU1") (pin "146") (pinfunction "146/GND_146") (pintype "bidirectional"))
      (node (ref "CPU1") (pin "151") (pinfunction "151/GND_151") (pintype "bidirectional"))
      (node (ref "CPU1") (pin "152") (pinfunction "152/GND_152") (pintype "bidirectional"))
      (node (ref "CPU1") (pin "157") (pinfunction "157/GND_157") (pintype "bidirectional"))
      (node (ref "CPU1") (pin "163") (pinfunction "163/GND_163") (pintype "bidirectional"))
      (node (ref "CPU1") (pin "164") (pinfunction "164/GND_164") (pintype "bidirectional"))
      (node (ref "CPU1") (pin "169") (pinfunction "169/GND_169") (pintype "bidirectional"))
      (node (ref "CPU1") (pin "170") (pinfunction "170/GND_170") (pintype "bidirectional"))
      (node (ref "CPU1") (pin "181") (pinfunction "181/GND_181") (pintype "bidirectional"))
      (node (ref "CPU1") (pin "182") (pinfunction "182/GND_182") (pintype "bidirectional"))
      (node (ref "CPU1") (pin "187") (pinfunction "187/GND_187") (pintype "bidirectional"))
      (node (ref "CPU1") (pin "188") (pinfunction "188/GND_188") (pintype "bidirectional"))
      (node (ref "CPU1") (pin "19") (pinfunction "19/GND_19") (pintype "bidirectional"))
      (node (ref "CPU1") (pin "195") (pinfunction "195/GND_195") (pintype "bidirectional"))
      (node (ref "CPU1") (pin "196") (pinfunction "196/GND_196") (pintype "bidirectional"))
      (node (ref "CPU1") (pin "20") (pinfunction "20/NC_20") (pintype "bidirectional"))
      (node (ref "CPU1") (pin "25") (pinfunction "25/GND_25") (pintype "bidirectional"))
      (node (ref "CPU1") (pin "26") (pinfunction "26/GND_26") (pintype "bidirectional"))
      (node (ref "CPU1") (pin "31") (pinfunction "31/GND_31") (pintype "bidirectional"))
      (node (ref "CPU1") (pin "32") (pinfunction "32/GND_32") (pintype "bidirectional"))
      (node (ref "CPU1") (pin "37") (pinfunction "37/GND_37") (pintype "bidirectional"))
      (node (ref "CPU1") (pin "38") (pinfunction "38/GND_38") (pintype "bidirectional"))
      (node (ref "CPU1") (pin "43") (pinfunction "43/GND_43") (pintype "bidirectional"))
      (node (ref "CPU1") (pin "44") (pinfunction "44/GND_44") (pintype "bidirectional"))
      (node (ref "CPU1") (pin "49") (pinfunction "49/GND_49") (pintype "bidirectional"))
      (node (ref "CPU1") (pin "50") (pinfunction "50/GND_50") (pintype "bidirectional"))
      (node (ref "CPU1") (pin "55") (pinfunction "55/GND_55") (pintype "bidirectional"))
      (node (ref "CPU1") (pin "56") (pinfunction "56/GND_56") (pintype "bidirectional"))
      (node (ref "CPU1") (pin "61") (pinfunction "61/GND_61") (pintype "bidirectional"))
      (node (ref "CPU1") (pin "62") (pinfunction "62/GND_62") (pintype "bidirectional"))
      (node (ref "CPU1") (pin "67") (pinfunction "67/GND_67") (pintype "bidirectional"))
      (node (ref "CPU1") (pin "68") (pinfunction "68/GND_68") (pintype "bidirectional"))
      (node (ref "CPU1") (pin "7") (pinfunction "7/GND_7") (pintype "bidirectional"))
      (node (ref "CPU1") (pin "73") (pinfunction "73/GND_73") (pintype "bidirectional"))
      (node (ref "CPU1") (pin "74") (pinfunction "74/GND_74") (pintype "bidirectional"))
      (node (ref "CPU1") (pin "79") (pinfunction "79/GND_79") (pintype "bidirectional"))
      (node (ref "CPU1") (pin "8") (pinfunction "8/NC_8") (pintype "bidirectional"))
      (node (ref "CPU1") (pin "80") (pinfunction "80/GND_80") (pintype "bidirectional"))
      (node (ref "CPU1") (pin "85") (pinfunction "85/GND_85") (pintype "bidirectional"))
      (node (ref "CPU1") (pin "86") (pinfunction "86/GND_86") (pintype "bidirectional"))
      (node (ref "CPU1") (pin "91") (pinfunction "91/GND_91") (pintype "bidirectional"))
      (node (ref "CPU1") (pin "92") (pinfunction "92/GND_92") (pintype "bidirectional"))
      (node (ref "CPU1") (pin "97") (pinfunction "97/GND_97") (pintype "bidirectional"))
      (node (ref "CPU1") (pin "98") (pinfunction "98/GND_98") (pintype "bidirectional"))
      (node (ref "IC1") (pin "B2") (pinfunction "GND_1_B2") (pintype "power_in"))
      (node (ref "IC1") (pin "C2") (pinfunction "GND_2_C2") (pintype "power_in"))
      (node (ref "IC4") (pin "5") (pinfunction "GND_5") (pintype "power_in"))
      (node (ref "IC5") (pin "6") (pinfunction "GND_6") (pintype "power_in"))
      (node (ref "IC8") (pin "1") (pinfunction "GND_1") (pintype "bidirectional"))
      (node (ref "J1") (pin "GND") (pinfunction "GND_GND") (pintype "power_in"))
      (node (ref "J1") (pin "SHLD1") (pinfunction "SHIELD_SHLD1") (pintype "bidirectional"))
      (node (ref "J1") (pin "SHLD2") (pinfunction "SHIELD_SHLD2") (pintype "bidirectional"))
      (node (ref "J2") (pin "GND") (pinfunction "GND_GND") (pintype "power_in"))
      (node (ref "J2") (pin "SHLD1") (pinfunction "SHIELD_SHLD1") (pintype "bidirectional"))
      (node (ref "J2") (pin "SHLD2") (pinfunction "SHIELD_SHLD2") (pintype "bidirectional"))
      (node (ref "J3") (pin "GND") (pinfunction "GND_GND") (pintype "power_in"))
      (node (ref "J3") (pin "MT1") (pinfunction "SHIELD_MT1") (pintype "bidirectional"))
      (node (ref "J3") (pin "MT2") (pinfunction "SHIELD_MT2") (pintype "bidirectional"))
      (node (ref "J3") (pin "P$1") (pinfunction "SHIELD_P$1") (pintype "bidirectional"))
      (node (ref "J3") (pin "P$2") (pinfunction "SHIELD_P$2") (pintype "bidirectional"))
      (node (ref "J5") (pin "M1") (pinfunction "SHIELD_M1") (pintype "bidirectional"))
      (node (ref "J5") (pin "M2") (pinfunction "SHIELD_M2") (pintype "bidirectional"))
      (node (ref "J6") (pin "6") (pinfunction "VSS_6") (pintype "passive"))
      (node (ref "J6") (pin "SH1") (pinfunction "SHIELD_SH1") (pintype "passive"))
      (node (ref "J6") (pin "SH2") (pinfunction "SHIELD_SH2") (pintype "passive"))
      (node (ref "J6") (pin "SH3") (pinfunction "SHIELD_SH3") (pintype "passive"))
      (node (ref "J6") (pin "SH4") (pinfunction "SHIELD_SH4") (pintype "passive"))
      (node (ref "J6") (pin "SH5") (pinfunction "SHIELD_SH5") (pintype "passive"))
      (node (ref "J7") (pin "1") (pinfunction "1_1") (pintype "passive"))
      (node (ref "J7") (pin "10") (pinfunction "10_10") (pintype "passive"))
      (node (ref "J7") (pin "11") (pinfunction "11_11") (pintype "passive"))
      (node (ref "J7") (pin "14") (pinfunction "14_14") (pintype "passive"))
      (node (ref "J7") (pin "17") (pinfunction "17_17") (pintype "passive"))
      (node (ref "J7") (pin "2") (pinfunction "2_2") (pintype "passive"))
      (node (ref "J7") (pin "3") (pinfunction "3_3") (pintype "passive"))
      (node (ref "J7") (pin "6") (pinfunction "6_6") (pintype "passive"))
      (node (ref "J7") (pin "7") (pinfunction "7_7") (pintype "passive"))
      (node (ref "J8") (pin "1") (pinfunction "1_1") (pintype "passive"))
      (node (ref "J8") (pin "10") (pinfunction "10_10") (pintype "passive"))
      (node (ref "J8") (pin "13") (pinfunction "13_13") (pintype "passive"))
      (node (ref "J8") (pin "17") (pinfunction "17_17") (pintype "passive"))
      (node (ref "J8") (pin "4") (pinfunction "4_4") (pintype "passive"))
      (node (ref "J8") (pin "7") (pinfunction "7_7") (pintype "passive"))
      (node (ref "JP1") (pin "3") (pinfunction "3_3") (pintype "passive"))
      (node (ref "JP2") (pin "3") (pinfunction "3_3") (pintype "passive"))
      (node (ref "Q1") (pin "3") (pinfunction "D_3") (pintype "bidirectional"))
      (node (ref "Q3") (pin "2") (pinfunction "S_2") (pintype "bidirectional"))
      (node (ref "Q5") (pin "2") (pinfunction "S_2") (pintype "bidirectional"))
      (node (ref "R1") (pin "1") (pinfunction "1_1") (pintype "passive"))
      (node (ref "R13") (pin "1") (pinfunction "1_1") (pintype "passive"))
      (node (ref "R14") (pin "1") (pinfunction "1_1") (pintype "passive"))
      (node (ref "R16") (pin "1") (pinfunction "1_1") (pintype "passive"))
      (node (ref "R19") (pin "1") (pinfunction "1_1") (pintype "passive"))
      (node (ref "R22") (pin "2") (pinfunction "2_2") (pintype "passive"))
      (node (ref "R23") (pin "2") (pinfunction "2_2") (pintype "passive"))
      (node (ref "R24") (pin "2") (pinfunction "2_2") (pintype "passive"))
      (node (ref "R25") (pin "2") (pinfunction "2_2") (pintype "passive"))
      (node (ref "R26") (pin "1") (pinfunction "1_1") (pintype "passive"))
      (node (ref "R27") (pin "2") (pinfunction "2_2") (pintype "passive"))
      (node (ref "R31") (pin "1") (pinfunction "1_1") (pintype "passive"))
      (node (ref "U$6") (pin "P$11") (pinfunction "CLOCKSHIELD_P$11") (pintype "bidirectional"))
      (node (ref "U$6") (pin "P$17") (pinfunction "CECGND_P$17") (pintype "bidirectional"))
      (node (ref "U$6") (pin "P$2") (pinfunction "DATA2SHIELD_P$2") (pintype "bidirectional"))
      (node (ref "U$6") (pin "P$5") (pinfunction "DATA1SHIELD_P$5") (pintype "bidirectional"))
      (node (ref "U$6") (pin "P$8") (pinfunction "DATA0SHIELD_P$8") (pintype "bidirectional"))
      (node (ref "U5") (pin "34") (pinfunction "TEST2_34") (pintype "passive"))
      (node (ref "U5") (pin "65") (pinfunction "EPAD_65") (pintype "passive"))
      (node (ref "U6") (pin "3") (pinfunction "GND_3") (pintype "power_in"))
      (node (ref "Y2") (pin "2") (pinfunction "3_2") (pintype "passive"))
      (node (ref "Y2") (pin "4") (pinfunction "3_4") (pintype "passive"))
    )
    (net (code "37") (name "GPIO0") (class "Default")
      (node (ref "CAM1") (pin "21") (pinfunction "21_21") (pintype "bidirectional"))
      (node (ref "CPU1") (pin "3") (pinfunction "3/GPIO0_3") (pintype "bidirectional"))
      (node (ref "R8") (pin "1") (pinfunction "1_1") (pintype "passive"))
    )
    (net (code "38") (name "GPIO1") (class "Default")
      (node (ref "CAM1") (pin "20") (pinfunction "20_20") (pintype "bidirectional"))
      (node (ref "CPU1") (pin "5") (pinfunction "5/GPIO1_5") (pintype "bidirectional"))
      (node (ref "R7") (pin "1") (pinfunction "1_1") (pintype "passive"))
    )
    (net (code "39") (name "GPIO4") (class "Default")
      (node (ref "CAM1") (pin "18") (pinfunction "18_18") (pintype "bidirectional"))
      (node (ref "CPU1") (pin "15") (pinfunction "15/GPIO4_15") (pintype "bidirectional"))
    )
    (net (code "40") (name "GPIO5") (class "Default")
      (node (ref "CAM1") (pin "17") (pinfunction "17_17") (pintype "bidirectional"))
      (node (ref "CPU1") (pin "17") (pinfunction "17/GPIO5_17") (pintype "bidirectional"))
    )
    (net (code "41") (name "GPIO6") (class "Default")
      (node (ref "CPU1") (pin "21") (pinfunction "21/GPIO6_21") (pintype "bidirectional"))
    )
    (net (code "42") (name "GPIO7") (class "Default")
      (node (ref "CPU1") (pin "23") (pinfunction "23/GPIO7_23") (pintype "bidirectional"))
    )
    (net (code "43") (name "GPIO8") (class "Default")
      (node (ref "CPU1") (pin "27") (pinfunction "27/GPIO8_27") (pintype "bidirectional"))
    )
    (net (code "44") (name "GPIO12") (class "Default")
      (node (ref "CPU1") (pin "45") (pinfunction "45/GPIO12_45") (pintype "bidirectional"))
    )
    (net (code "45") (name "GPIO13") (class "Default")
      (node (ref "CPU1") (pin "47") (pinfunction "47/GPIO13_47") (pintype "bidirectional"))
    )
    (net (code "46") (name "GPIO14") (class "Default")
      (node (ref "CPU1") (pin "51") (pinfunction "51/GPIO14_51") (pintype "bidirectional"))
    )
    (net (code "47") (name "GPIO15") (class "Default")
      (node (ref "CPU1") (pin "53") (pinfunction "53/GPIO15_53") (pintype "bidirectional"))
    )
    (net (code "48") (name "GPIO16") (class "Default")
      (node (ref "CPU1") (pin "57") (pinfunction "57/GPIO16_57") (pintype "bidirectional"))
    )
    (net (code "49") (name "GPIO17") (class "Default")
      (node (ref "CPU1") (pin "59") (pinfunction "59/GPIO17_59") (pintype "bidirectional"))
    )
    (net (code "50") (name "GPIO18") (class "Default")
      (node (ref "CPU1") (pin "63") (pinfunction "63/GPIO18_63") (pintype "bidirectional"))
    )
    (net (code "51") (name "GPIO22") (class "Default")
      (node (ref "CPU1") (pin "75") (pinfunction "75/GPIO22_75") (pintype "bidirectional"))
    )
    (net (code "52") (name "GPIO23") (class "Default")
      (node (ref "CPU1") (pin "77") (pinfunction "77/GPIO23_77") (pintype "bidirectional"))
    )
    (net (code "53") (name "GPIO24") (class "Default")
      (node (ref "CPU1") (pin "81") (pinfunction "81/GPIO24_81") (pintype "bidirectional"))
    )
    (net (code "54") (name "GPIO25") (class "Default")
      (node (ref "CPU1") (pin "83") (pinfunction "83/GPIO25_83") (pintype "bidirectional"))
    )
    (net (code "55") (name "GPIO26") (class "Default")
      (node (ref "CPU1") (pin "87") (pinfunction "87/GPIO26_87") (pintype "bidirectional"))
    )
    (net (code "56") (name "GPIO27") (class "Default")
      (node (ref "CPU1") (pin "89") (pinfunction "89/GPIO27_89") (pintype "bidirectional"))
    )
    (net (code "57") (name "GPIO28") (class "Default")
      (node (ref "CAM0") (pin "21") (pinfunction "21_21") (pintype "bidirectional"))
      (node (ref "CPU1") (pin "28") (pinfunction "28/GPIO28_28") (pintype "bidirectional"))
      (node (ref "R22") (pin "1") (pinfunction "1_1") (pintype "passive"))
    )
    (net (code "58") (name "GPIO29") (class "Default")
      (node (ref "CAM0") (pin "20") (pinfunction "20_20") (pintype "bidirectional"))
      (node (ref "CPU1") (pin "30") (pinfunction "30/GPIO29_30") (pintype "bidirectional"))
      (node (ref "R23") (pin "1") (pinfunction "1_1") (pintype "passive"))
    )
    (net (code "59") (name "GPIO30") (class "Default")
      (node (ref "CAM0") (pin "18") (pinfunction "18_18") (pintype "bidirectional"))
      (node (ref "CPU1") (pin "34") (pinfunction "34/GPIO30_34") (pintype "bidirectional"))
    )
    (net (code "60") (name "GPIO31") (class "Default")
      (node (ref "CAM0") (pin "17") (pinfunction "17_17") (pintype "bidirectional"))
      (node (ref "CPU1") (pin "36") (pinfunction "36/GPIO31_36") (pintype "bidirectional"))
    )
    (net (code "61") (name "GPIO32") (class "Default")
      (node (ref "CPU1") (pin "46") (pinfunction "46/GPIO32_46") (pintype "bidirectional"))
      (node (ref "J8") (pin "12") (pinfunction "12_12") (pintype "passive"))
    )
    (net (code "62") (name "GPIO33") (class "Default")
      (node (ref "CPU1") (pin "48") (pinfunction "48/GPIO33_48") (pintype "bidirectional"))
      (node (ref "J8") (pin "11") (pinfunction "11_11") (pintype "passive"))
    )
    (net (code "63") (name "GPIO34") (class "Default")
      (node (ref "CPU1") (pin "52") (pinfunction "52/GPIO34_52") (pintype "bidirectional"))
      (node (ref "J8") (pin "9") (pinfunction "9_9") (pintype "passive"))
    )
    (net (code "64") (name "GPIO35") (class "Default")
      (node (ref "CPU1") (pin "54") (pinfunction "54/GPIO35_54") (pintype "bidirectional"))
      (node (ref "J8") (pin "8") (pinfunction "8_8") (pintype "passive"))
    )
    (net (code "65") (name "GPIO36") (class "Default")
      (node (ref "CPU1") (pin "58") (pinfunction "58/GPIO36_58") (pintype "bidirectional"))
      (node (ref "J8") (pin "6") (pinfunction "6_6") (pintype "passive"))
    )
    (net (code "66") (name "GPIO37") (class "Default")
      (node (ref "CPU1") (pin "60") (pinfunction "60/GPIO37_60") (pintype "bidirectional"))
      (node (ref "J8") (pin "5") (pinfunction "5_5") (pintype "passive"))
    )
    (net (code "67") (name "GPIO38") (class "Default")
      (node (ref "CPU1") (pin "64") (pinfunction "64/GPIO38_64") (pintype "bidirectional"))
      (node (ref "J8") (pin "3") (pinfunction "3_3") (pintype "passive"))
    )
    (net (code "68") (name "GPIO39") (class "Default")
      (node (ref "CPU1") (pin "66") (pinfunction "66/GPIO39_66") (pintype "bidirectional"))
      (node (ref "J8") (pin "2") (pinfunction "2_2") (pintype "passive"))
    )
    (net (code "69") (name "GPIO40") (class "Default")
      (node (ref "CPU1") (pin "70") (pinfunction "70/GPIO40_70") (pintype "bidirectional"))
    )
    (net (code "70") (name "GPIO41") (class "Default")
      (node (ref "CPU1") (pin "72") (pinfunction "72/GPIO41_72") (pintype "bidirectional"))
    )
    (net (code "71") (name "GPIO42") (class "Default")
      (node (ref "CPU1") (pin "76") (pinfunction "76/GPIO42_76") (pintype "bidirectional"))
    )
    (net (code "72") (name "GPIO43") (class "Default")
      (node (ref "CPU1") (pin "78") (pinfunction "78/GPIO43_78") (pintype "bidirectional"))
    )
    (net (code "73") (name "GPIO44") (class "Default")
      (node (ref "CPU1") (pin "82") (pinfunction "82/GPIO44_82") (pintype "bidirectional"))
      (node (ref "R24") (pin "1") (pinfunction "1_1") (pintype "passive"))
    )
    (net (code "74") (name "GPIO45") (class "Default")
      (node (ref "CPU1") (pin "84") (pinfunction "84/GPIO45_84") (pintype "bidirectional"))
      (node (ref "R25") (pin "1") (pinfunction "1_1") (pintype "passive"))
    )
    (net (code "75") (name "H5V") (class "Default")
      (node (ref "C2") (pin "1") (pinfunction "1_1") (pintype "passive"))
      (node (ref "IC1") (pin "A1") (pinfunction "5V_A1") (pintype "bidirectional"))
      (node (ref "IC1") (pin "C1") (pinfunction "RPU_C1") (pintype "bidirectional"))
      (node (ref "IC8") (pin "2") (pinfunction "OUT_2") (pintype "bidirectional"))
      (node (ref "Q4") (pin "1") (pinfunction "G_1") (pintype "bidirectional"))
      (node (ref "U$6") (pin "P$18") (pinfunction "VCC_P$18") (pintype "bidirectional"))
    )
    (net (code "76") (name "HDMI_CEC") (class "Default")
      (node (ref "CPU1") (pin "171") (pinfunction "171/HDMI_CEC_171") (pintype "bidirectional"))
      (node (ref "Q4") (pin "2") (pinfunction "S_2") (pintype "bidirectional"))
    )
    (net (code "77") (name "HDMI_CK_N") (class "Default")
      (node (ref "CPU1") (pin "111") (pinfunction "111/HDMI_CK_N*_111") (pintype "bidirectional"))
      (node (ref "U$6") (pin "P$12") (pinfunction "CLOCK-_P$12") (pintype "bidirectional"))
    )
    (net (code "78") (name "HDMI_CK_P") (class "Default")
      (node (ref "CPU1") (pin "113") (pinfunction "113/HDMI_CK_P*_113") (pintype "bidirectional"))
      (node (ref "U$6") (pin "P$10") (pinfunction "CLOCK+_P$10") (pintype "bidirectional"))
    )
    (net (code "79") (name "HDMI_D0_N") (class "Default")
      (node (ref "CPU1") (pin "117") (pinfunction "117/HDMI_D0_N*_117") (pintype "bidirectional"))
      (node (ref "U$6") (pin "P$9") (pinfunction "DATA0-_P$9") (pintype "bidirectional"))
    )
    (net (code "80") (name "HDMI_D0_P") (class "Default")
      (node (ref "CPU1") (pin "119") (pinfunction "119/HDMI_D0_P*_119") (pintype "bidirectional"))
      (node (ref "U$6") (pin "P$7") (pinfunction "DATA0+_P$7") (pintype "bidirectional"))
    )
    (net (code "81") (name "HDMI_D1_N") (class "Default")
      (node (ref "CPU1") (pin "123") (pinfunction "123/HDMI_D1_N*_123") (pintype "bidirectional"))
      (node (ref "U$6") (pin "P$6") (pinfunction "DATA1-_P$6") (pintype "bidirectional"))
    )
    (net (code "82") (name "HDMI_D1_P") (class "Default")
      (node (ref "CPU1") (pin "125") (pinfunction "125/HDMI_D1_P*_125") (pintype "bidirectional"))
      (node (ref "U$6") (pin "P$4") (pinfunction "DATA1+_P$4") (pintype "bidirectional"))
    )
    (net (code "83") (name "HDMI_D2_N") (class "Default")
      (node (ref "CPU1") (pin "129") (pinfunction "129/HDMI_D2_N*_129") (pintype "bidirectional"))
      (node (ref "U$6") (pin "P$3") (pinfunction "DATA2-_P$3") (pintype "bidirectional"))
    )
    (net (code "84") (name "HDMI_D2_P") (class "Default")
      (node (ref "CPU1") (pin "131") (pinfunction "131/HDMI_D2_P*_131") (pintype "bidirectional"))
      (node (ref "U$6") (pin "P$1") (pinfunction "DATA2+_P$1") (pintype "bidirectional"))
    )
    (net (code "85") (name "HDMI_HPD_N_1V8") (class "Default")
      (node (ref "CPU1") (pin "88") (pinfunction "88/GPIO46_1V8_88") (pintype "bidirectional"))
      (node (ref "Q5") (pin "3") (pinfunction "D_3") (pintype "bidirectional"))
      (node (ref "R2") (pin "2") (pinfunction "2_2") (pintype "passive"))
    )
    (net (code "86") (name "HDMI_SCL") (class "Default")
      (node (ref "CPU1") (pin "175") (pinfunction "175/HDMI_SCL_175") (pintype "bidirectional"))
      (node (ref "IC1") (pin "B3") (pinfunction "SDA_B3") (pintype "bidirectional"))
      (node (ref "U$6") (pin "P$16") (pinfunction "SDA_P$16") (pintype "bidirectional"))
    )
    (net (code "87") (name "HDMI_SDA") (class "Default")
      (node (ref "CPU1") (pin "173") (pinfunction "173/HDMI_SDA_173") (pintype "bidirectional"))
      (node (ref "IC1") (pin "A3") (pinfunction "SCL_A3") (pintype "bidirectional"))
      (node (ref "U$6") (pin "P$15") (pinfunction "SCL_P$15") (pintype "bidirectional"))
    )
    (net (code "88") (name "NLNKA") (class "Default")
      (node (ref "R15") (pin "2") (pinfunction "2_2") (pintype "passive"))
      (node (ref "U5") (pin "21") (pinfunction "NLNKA_LED/GPIO1_21") (pintype "bidirectional"))
    )
    (net (code "89") (name "NRESET") (class "Default")
      (node (ref "U5") (pin "12") (pinfunction "NRESET_12") (pintype "input"))
    )
    (net (code "90") (name "NSPD") (class "Default")
      (node (ref "R12") (pin "2") (pinfunction "2_2") (pintype "passive"))
      (node (ref "U5") (pin "22") (pinfunction "NSPD_LED/GPIO2_22") (pintype "bidirectional"))
    )
    (net (code "91") (name "Net-(D7-PadC)") (class "Default")
      (node (ref "D7") (pin "C") (pinfunction "C_C") (pintype "passive"))
      (node (ref "R14") (pin "2") (pinfunction "2_2") (pintype "passive"))
    )
    (net (code "92") (name "Net-(D8-PadC)") (class "Default")
      (node (ref "D8") (pin "C") (pinfunction "C_C") (pintype "passive"))
      (node (ref "R13") (pin "2") (pinfunction "2_2") (pintype "passive"))
    )
    (net (code "93") (name "Net-(D9-PadA)") (class "Default")
      (node (ref "D9") (pin "A") (pinfunction "A_A") (pintype "passive"))
      (node (ref "R20") (pin "1") (pinfunction "1_1") (pintype "passive"))
    )
    (net (code "94") (name "Net-(D10-FULLDUPLEX-PadC)") (class "Default")
      (node (ref "D10-FULLDUPLEX") (pin "C") (pinfunction "C_C") (pintype "passive"))
      (node (ref "R32") (pin "2") (pinfunction "2_2") (pintype "passive"))
    )
    (net (code "95") (name "Net-(IC1-CEC)") (class "Default")
      (node (ref "IC1") (pin "A2") (pinfunction "CEC_A2") (pintype "bidirectional"))
      (node (ref "Q4") (pin "3") (pinfunction "D_3") (pintype "bidirectional"))
      (node (ref "U$6") (pin "P$13") (pinfunction "CEC_P$13") (pintype "bidirectional"))
    )
    (net (code "96") (name "Net-(IC1-HPD)") (class "Default")
      (node (ref "IC1") (pin "C3") (pinfunction "HPD_C3") (pintype "bidirectional"))
      (node (ref "Q5") (pin "1") (pinfunction "G_1") (pintype "bidirectional"))
      (node (ref "U$6") (pin "P$19") (pinfunction "HOTPLUG_P$19") (pintype "bidirectional"))
    )
    (net (code "97") (name "Net-(IC5-ENA)") (class "Default")
      (node (ref "IC5") (pin "1") (pinfunction "ENA_1") (pintype "input"))
      (node (ref "IC5") (pin "2") (pinfunction "FLGA_2") (pintype "open_collector"))
      (node (ref "U5") (pin "14") (pinfunction "PRTXTL2_14") (pintype "bidirectional"))
    )
    (net (code "98") (name "Net-(IC5-ENB)") (class "Default")
      (node (ref "IC5") (pin "3") (pinfunction "FLGB_3") (pintype "open_collector"))
      (node (ref "IC5") (pin "4") (pinfunction "ENB_4") (pintype "input"))
      (node (ref "U5") (pin "16") (pinfunction "PRTCTL3_16") (pintype "bidirectional"))
    )
    (net (code "99") (name "Net-(IC5-OUTA)") (class "Default")
      (node (ref "C37") (pin "1") (pinfunction "1_1") (pintype "passive"))
      (node (ref "D8") (pin "A") (pinfunction "A_A") (pintype "passive"))
      (node (ref "IC5") (pin "8") (pinfunction "OUTA_8") (pintype "output"))
      (node (ref "J2") (pin "VBUS") (pinfunction "VBUS_VBUS") (pintype "power_in"))
    )
    (net (code "100") (name "Net-(IC5-OUTB)") (class "Default")
      (node (ref "C38") (pin "1") (pinfunction "1_1") (pintype "passive"))
      (node (ref "D7") (pin "A") (pinfunction "A_A") (pintype "passive"))
      (node (ref "IC5") (pin "5") (pinfunction "OUTB_5") (pintype "output"))
      (node (ref "J1") (pin "VBUS") (pinfunction "VBUS_VBUS") (pintype "power_in"))
    )
    (net (code "101") (name "Net-(J5-GLED-)") (class "Default")
      (node (ref "J5") (pin "12") (pinfunction "GLED-_12") (pintype "bidirectional"))
      (node (ref "R15") (pin "1") (pinfunction "1_1") (pintype "passive"))
    )
    (net (code "102") (name "Net-(J5-RCT)") (class "Default")
      (node (ref "C3") (pin "2") (pinfunction "2_2") (pintype "passive"))
      (node (ref "J5") (pin "3") (pinfunction "RCT_3") (pintype "bidirectional"))
      (node (ref "J5") (pin "6") (pinfunction "TCT_6") (pintype "bidirectional"))
      (node (ref "R9") (pin "1") (pinfunction "1_1") (pintype "passive"))
    )
    (net (code "103") (name "Net-(J5-YLED-)") (class "Default")
      (node (ref "J5") (pin "10") (pinfunction "YLED-_10") (pintype "bidirectional"))
      (node (ref "R12") (pin "1") (pinfunction "1_1") (pintype "passive"))
    )
    (net (code "104") (name "Net-(JP2-Pad2)") (class "Default")
      (node (ref "JP2") (pin "2") (pinfunction "2_2") (pintype "passive"))
      (node (ref "R30") (pin "1") (pinfunction "1_1") (pintype "passive"))
    )
    (net (code "105") (name "Net-(PWR_LED-PadC)") (class "Default")
      (node (ref "PWR_LED") (pin "C") (pinfunction "C_C") (pintype "passive"))
      (node (ref "R1") (pin "2") (pinfunction "2_2") (pintype "passive"))
    )
    (net (code "106") (name "Net-(Q1-S)") (class "Default")
      (node (ref "Q1") (pin "2") (pinfunction "S_2") (pintype "bidirectional"))
      (node (ref "R17") (pin "1") (pinfunction "1_1") (pintype "passive"))
      (node (ref "U6") (pin "10") (pinfunction "SEL_10") (pintype "input"))
    )
    (net (code "107") (name "Net-(Q2-G)") (class "Default")
      (node (ref "JP1") (pin "2") (pinfunction "2_2") (pintype "passive"))
      (node (ref "Q2") (pin "1") (pinfunction "G_1") (pintype "bidirectional"))
      (node (ref "R19") (pin "2") (pinfunction "2_2") (pintype "passive"))
    )
    (net (code "108") (name "Net-(Q2-S)") (class "Default")
      (node (ref "D9") (pin "C") (pinfunction "C_C") (pintype "passive"))
      (node (ref "Q2") (pin "2") (pinfunction "S_2") (pintype "bidirectional"))
      (node (ref "Q3") (pin "3") (pinfunction "D_3") (pintype "bidirectional"))
    )
    (net (code "109") (name "Net-(U5-AUTOMDIX_EN)") (class "Default")
      (node (ref "R30") (pin "2") (pinfunction "2_2") (pintype "passive"))
      (node (ref "U5") (pin "41") (pinfunction "AUTOMDIX_EN_41") (pintype "input"))
    )
    (net (code "110") (name "Net-(U5-EXRES)") (class "Default")
      (node (ref "R26") (pin "2") (pinfunction "2_2") (pintype "passive"))
      (node (ref "U5") (pin "50") (pinfunction "EXRES_50") (pintype "input"))
    )
    (net (code "111") (name "Net-(U5-NFDX_LED{slash}GPIO0)") (class "Default")
      (node (ref "R32") (pin "1") (pinfunction "1_1") (pintype "passive"))
      (node (ref "U5") (pin "20") (pinfunction "NFDX_LED/GPIO0_20") (pintype "bidirectional"))
    )
    (net (code "112") (name "Net-(U5-USBRBIAS)") (class "Default")
      (node (ref "R31") (pin "2") (pinfunction "2_2") (pintype "passive"))
      (node (ref "U5") (pin "63") (pinfunction "USBRBIAS_63") (pintype "input"))
    )
    (net (code "113") (name "Net-(U5-VBUS_DET)") (class "Default")
      (node (ref "R28") (pin "2") (pinfunction "2_2") (pintype "passive"))
      (node (ref "U5") (pin "11") (pinfunction "VBUS_DET_11") (pintype "power_in"))
    )
    (net (code "114") (name "Net-(U5-XI)") (class "Default")
      (node (ref "C35") (pin "1") (pinfunction "1_1") (pintype "passive"))
      (node (ref "R29") (pin "1") (pinfunction "1_1") (pintype "passive"))
      (node (ref "U5") (pin "61") (pinfunction "XI_61") (pintype "input"))
      (node (ref "Y2") (pin "1") (pinfunction "1_1") (pintype "passive"))
    )
    (net (code "115") (name "Net-(U5-XO)") (class "Default")
      (node (ref "C36") (pin "1") (pinfunction "1_1") (pintype "passive"))
      (node (ref "R29") (pin "2") (pinfunction "2_2") (pintype "passive"))
      (node (ref "U5") (pin "60") (pinfunction "XO_60") (pintype "output"))
      (node (ref "Y2") (pin "3") (pinfunction "2_3") (pintype "passive"))
    )
    (net (code "116") (name "Net-(U6-HSD2+)") (class "Default")
      (node (ref "J3") (pin "D+") (pinfunction "D+_D+") (pintype "bidirectional"))
      (node (ref "U6") (pin "7") (pinfunction "HSD2+_7") (pintype "input"))
    )
    (net (code "117") (name "Net-(U6-HSD2-)") (class "Default")
      (node (ref "J3") (pin "D-") (pinfunction "D-_D-") (pintype "bidirectional"))
      (node (ref "U6") (pin "6") (pinfunction "HSD2-_6") (pintype "input"))
    )
    (net (code "118") (name "RX_N") (class "Default")
      (node (ref "J5") (pin "2") (pinfunction "RD-_2") (pintype "bidirectional"))
      (node (ref "R6") (pin "1") (pinfunction "1_1") (pintype "passive"))
      (node (ref "U5") (pin "53") (pinfunction "RXN_53") (pintype "bidirectional"))
    )
    (net (code "119") (name "RX_P") (class "Default")
      (node (ref "J5") (pin "1") (pinfunction "RD+_1") (pintype "bidirectional"))
      (node (ref "R5") (pin "1") (pinfunction "1_1") (pintype "passive"))
      (node (ref "U5") (pin "52") (pinfunction "RXP_52") (pintype "bidirectional"))
    )
    (net (code "120") (name "SCL0") (class "Default")
      (node (ref "J7") (pin "15") (pinfunction "15_15") (pintype "passive"))
    )
    (net (code "121") (name "SCL1") (class "Default")
      (node (ref "CPU1") (pin "11") (pinfunction "11/GPIO3_11") (pintype "bidirectional"))
      (node (ref "J7") (pin "12") (pinfunction "12_12") (pintype "passive"))
      (node (ref "R10") (pin "1") (pinfunction "1_1") (pintype "passive"))
    )
    (net (code "122") (name "SDA0") (class "Default")
      (node (ref "J7") (pin "16") (pinfunction "16_16") (pintype "passive"))
    )
    (net (code "123") (name "SDA1") (class "Default")
      (node (ref "CPU1") (pin "9") (pinfunction "9/GPIO2_9") (pintype "bidirectional"))
      (node (ref "J7") (pin "13") (pinfunction "13_13") (pintype "passive"))
      (node (ref "R11") (pin "1") (pinfunction "1_1") (pintype "passive"))
    )
    (net (code "124") (name "SD_CLK") (class "Default")
      (node (ref "CPU1") (pin "10") (pinfunction "10/NC_10") (pintype "bidirectional"))
      (node (ref "J6") (pin "5") (pinfunction "CLK_5") (pintype "passive"))
    )
    (net (code "125") (name "SD_CMD") (class "Default")
      (node (ref "CPU1") (pin "12") (pinfunction "12/NC_12") (pintype "bidirectional"))
      (node (ref "J6") (pin "3") (pinfunction "CMD_3") (pintype "passive"))
    )
    (net (code "126") (name "SD_D0") (class "Default")
      (node (ref "CPU1") (pin "16") (pinfunction "16/NC_16") (pintype "bidirectional"))
      (node (ref "J6") (pin "7") (pinfunction "DAT0_7") (pintype "passive"))
    )
    (net (code "127") (name "SD_D1") (class "Default")
      (node (ref "CPU1") (pin "18") (pinfunction "18/NC_18") (pintype "bidirectional"))
      (node (ref "J6") (pin "8") (pinfunction "DAT1_8") (pintype "passive"))
    )
    (net (code "128") (name "SD_D2") (class "Default")
      (node (ref "CPU1") (pin "22") (pinfunction "22/NC_22") (pintype "bidirectional"))
      (node (ref "J6") (pin "1") (pinfunction "DATA2_1") (pintype "passive"))
    )
    (net (code "129") (name "SD_D3") (class "Default")
      (node (ref "CPU1") (pin "24") (pinfunction "24/NC_24") (pintype "bidirectional"))
      (node (ref "J6") (pin "2") (pinfunction "CD/DAT3_2") (pintype "passive"))
    )
    (net (code "130") (name "SD_VREF") (class "Default")
      (node (ref "C13") (pin "2") (pinfunction "2_2") (pintype "passive"))
      (node (ref "CPU1") (pin "4") (pinfunction "4/NC_4") (pintype "bidirectional"))
      (node (ref "CPU1") (pin "6") (pinfunction "6/NC_6") (pintype "bidirectional"))
      (node (ref "SJ1") (pin "1") (pinfunction "1_1") (pintype "passive"))
    )
    (net (code "131") (name "SPI0_MISO") (class "Default")
      (node (ref "CPU1") (pin "29") (pinfunction "29/GPIO9_29") (pintype "bidirectional"))
      (node (ref "J8") (pin "19") (pinfunction "19_19") (pintype "passive"))
    )
    (net (code "132") (name "SPI0_MOSI") (class "Default")
      (node (ref "CPU1") (pin "33") (pinfunction "33/GPIO10_33") (pintype "bidirectional"))
      (node (ref "J8") (pin "20") (pinfunction "20_20") (pintype "passive"))
    )
    (net (code "133") (name "SPI0_SCLK") (class "Default")
      (node (ref "CPU1") (pin "35") (pinfunction "35/GPIO11_35") (pintype "bidirectional"))
      (node (ref "J8") (pin "18") (pinfunction "18_18") (pintype "passive"))
    )
    (net (code "134") (name "SPI1_MISO") (class "Default")
      (node (ref "CPU1") (pin "65") (pinfunction "65/GPIO19_65") (pintype "bidirectional"))
      (node (ref "J8") (pin "15") (pinfunction "15_15") (pintype "passive"))
    )
    (net (code "135") (name "SPI1_MOSI") (class "Default")
      (node (ref "CPU1") (pin "69") (pinfunction "69/GPIO20_69") (pintype "bidirectional"))
      (node (ref "J8") (pin "16") (pinfunction "16_16") (pintype "passive"))
    )
    (net (code "136") (name "SPI1_SCLK") (class "Default")
      (node (ref "CPU1") (pin "71") (pinfunction "71/GPIO21_71") (pintype "bidirectional"))
      (node (ref "J8") (pin "14") (pinfunction "14_14") (pintype "passive"))
    )
    (net (code "137") (name "TX_N") (class "Default")
      (node (ref "J5") (pin "8") (pinfunction "TD-_8") (pintype "bidirectional"))
      (node (ref "R4") (pin "1") (pinfunction "1_1") (pintype "passive"))
      (node (ref "U5") (pin "56") (pinfunction "TXN_56") (pintype "bidirectional"))
    )
    (net (code "138") (name "TX_P") (class "Default")
      (node (ref "J5") (pin "7") (pinfunction "TD+_7") (pintype "bidirectional"))
      (node (ref "R3") (pin "1") (pinfunction "1_1") (pintype "passive"))
      (node (ref "U5") (pin "55") (pinfunction "TXP_55") (pintype "bidirectional"))
    )
    (net (code "139") (name "USB_D_N") (class "Default")
      (node (ref "CPU1") (pin "167") (pinfunction "167/USB_DM**_167") (pintype "bidirectional"))
      (node (ref "U6") (pin "2") (pinfunction "D-_2") (pintype "bidirectional"))
    )
    (net (code "140") (name "USB_D_P") (class "Default")
      (node (ref "CPU1") (pin "165") (pinfunction "165/USB_DP**_165") (pintype "bidirectional"))
      (node (ref "U6") (pin "1") (pinfunction "D+_1") (pintype "bidirectional"))
    )
    (net (code "141") (name "VBUSB") (class "Default")
      (node (ref "J3") (pin "VBUS") (pinfunction "VBUS_VBUS") (pintype "power_in"))
      (node (ref "JP1") (pin "1") (pinfunction "1_1") (pintype "passive"))
      (node (ref "Q1") (pin "1") (pinfunction "G_1") (pintype "bidirectional"))
      (node (ref "R16") (pin "2") (pinfunction "2_2") (pintype "passive"))
    )
    (net (code "142") (name "unconnected-(CAM0-Pad11)") (class "Default")
      (node (ref "CAM0") (pin "11") (pinfunction "11_11") (pintype "bidirectional"))
    )
    (net (code "143") (name "unconnected-(CAM0-Pad12)") (class "Default")
      (node (ref "CAM0") (pin "12") (pinfunction "12_12") (pintype "bidirectional"))
    )
    (net (code "144") (name "unconnected-(CAM0-Pad14)") (class "Default")
      (node (ref "CAM0") (pin "14") (pinfunction "14_14") (pintype "bidirectional"))
    )
    (net (code "145") (name "unconnected-(CAM0-Pad15)") (class "Default")
      (node (ref "CAM0") (pin "15") (pinfunction "15_15") (pintype "bidirectional"))
    )
    (net (code "146") (name "unconnected-(CPU1-93{slash}DSI0_DN1*-Pad93)") (class "Default")
      (node (ref "CPU1") (pin "93") (pinfunction "93/DSI0_DN1*_93") (pintype "bidirectional"))
    )
    (net (code "147") (name "unconnected-(CPU1-94{slash}DSI1_DP0*-Pad94)") (class "Default")
      (node (ref "CPU1") (pin "94") (pinfunction "94/DSI1_DP0*_94") (pintype "bidirectional"))
    )
    (net (code "148") (name "unconnected-(CPU1-95{slash}DSI0_DP1*-Pad95)") (class "Default")
      (node (ref "CPU1") (pin "95") (pinfunction "95/DSI0_DP1*_95") (pintype "bidirectional"))
    )
    (net (code "149") (name "unconnected-(CPU1-96{slash}DSI1_DN0*-Pad96)") (class "Default")
      (node (ref "CPU1") (pin "96") (pinfunction "96/DSI1_DN0*_96") (pintype "bidirectional"))
    )
    (net (code "150") (name "unconnected-(CPU1-99{slash}DSI0_DN0*-Pad99)") (class "Default")
      (node (ref "CPU1") (pin "99") (pinfunction "99/DSI0_DN0*_99") (pintype "bidirectional"))
    )
    (net (code "151") (name "unconnected-(CPU1-100{slash}DSI1CP*-Pad100)") (class "Default")
      (node (ref "CPU1") (pin "100") (pinfunction "100/DSI1CP*_100") (pintype "bidirectional"))
    )
    (net (code "152") (name "unconnected-(CPU1-101{slash}DSI0_DP0*-Pad101)") (class "Default")
      (node (ref "CPU1") (pin "101") (pinfunction "101/DSI0_DP0*_101") (pintype "bidirectional"))
    )
    (net (code "153") (name "unconnected-(CPU1-102{slash}DSI1CN*-Pad102)") (class "Default")
      (node (ref "CPU1") (pin "102") (pinfunction "102/DSI1CN*_102") (pintype "bidirectional"))
    )
    (net (code "154") (name "unconnected-(CPU1-105{slash}DSI0_CN*-Pad105)") (class "Default")
      (node (ref "CPU1") (pin "105") (pinfunction "105/DSI0_CN*_105") (pintype "bidirectional"))
    )
    (net (code "155") (name "unconnected-(CPU1-106{slash}DSI1_DP3*-Pad106)") (class "Default")
      (node (ref "CPU1") (pin "106") (pinfunction "106/DSI1_DP3*_106") (pintype "bidirectional"))
    )
    (net (code "156") (name "unconnected-(CPU1-107{slash}DSI0_CP*-Pad107)") (class "Default")
      (node (ref "CPU1") (pin "107") (pinfunction "107/DSI0_CP*_107") (pintype "bidirectional"))
    )
    (net (code "157") (name "unconnected-(CPU1-108{slash}DSI1_DN3*-Pad108)") (class "Default")
      (node (ref "CPU1") (pin "108") (pinfunction "108/DSI1_DN3*_108") (pintype "bidirectional"))
    )
    (net (code "158") (name "unconnected-(CPU1-112{slash}DSI1_DP2*-Pad112)") (class "Default")
      (node (ref "CPU1") (pin "112") (pinfunction "112/DSI1_DP2*_112") (pintype "bidirectional"))
    )
    (net (code "159") (name "unconnected-(CPU1-114{slash}DSI1_DN2*-Pad114)") (class "Default")
      (node (ref "CPU1") (pin "114") (pinfunction "114/DSI1_DN2*_114") (pintype "bidirectional"))
    )
    (net (code "160") (name "unconnected-(CPU1-118{slash}DSI1_DP1*-Pad118)") (class "Default")
      (node (ref "CPU1") (pin "118") (pinfunction "118/DSI1_DP1*_118") (pintype "bidirectional"))
    )
    (net (code "161") (name "unconnected-(CPU1-120{slash}DSI1_DN1*-Pad120)") (class "Default")
      (node (ref "CPU1") (pin "120") (pinfunction "120/DSI1_DN1*_120") (pintype "bidirectional"))
    )
    (net (code "162") (name "unconnected-(CPU1-124{slash}NC-Pad124)") (class "Default")
      (node (ref "CPU1") (pin "124") (pinfunction "124/NC_124") (pintype "bidirectional"))
    )
    (net (code "163") (name "unconnected-(CPU1-126{slash}NC-Pad126)") (class "Default")
      (node (ref "CPU1") (pin "126") (pinfunction "126/NC_126") (pintype "bidirectional"))
    )
    (net (code "164") (name "unconnected-(CPU1-128{slash}NC-Pad128)") (class "Default")
      (node (ref "CPU1") (pin "128") (pinfunction "128/NC_128") (pintype "bidirectional"))
    )
    (net (code "165") (name "unconnected-(CPU1-130{slash}NC-Pad130)") (class "Default")
      (node (ref "CPU1") (pin "130") (pinfunction "130/NC_130") (pintype "bidirectional"))
    )
    (net (code "166") (name "unconnected-(CPU1-132{slash}NC-Pad132)") (class "Default")
      (node (ref "CPU1") (pin "132") (pinfunction "132/NC_132") (pintype "bidirectional"))
    )
    (net (code "167") (name "unconnected-(CPU1-154{slash}NC-Pad154)") (class "Default")
      (node (ref "CPU1") (pin "154") (pinfunction "154/NC_154") (pintype "bidirectional"))
    )
    (net (code "168") (name "unconnected-(CPU1-156{slash}NC-Pad156)") (class "Default")
      (node (ref "CPU1") (pin "156") (pinfunction "156/NC_156") (pintype "bidirectional"))
    )
    (net (code "169") (name "unconnected-(CPU1-158{slash}NC-Pad158)") (class "Default")
      (node (ref "CPU1") (pin "158") (pinfunction "158/NC_158") (pintype "bidirectional"))
    )
    (net (code "170") (name "unconnected-(CPU1-160{slash}NC-Pad160)") (class "Default")
      (node (ref "CPU1") (pin "160") (pinfunction "160/NC_160") (pintype "bidirectional"))
    )
    (net (code "171") (name "unconnected-(CPU1-162{slash}NC-Pad162)") (class "Default")
      (node (ref "CPU1") (pin "162") (pinfunction "162/NC_162") (pintype "bidirectional"))
    )
    (net (code "172") (name "unconnected-(CPU1-166{slash}TVDAC-Pad166)") (class "Default")
      (node (ref "CPU1") (pin "166") (pinfunction "166/TVDAC_166") (pintype "bidirectional"))
    )
    (net (code "173") (name "unconnected-(CPU1-168{slash}USB_OTGID-Pad168)") (class "Default")
      (node (ref "CPU1") (pin "168") (pinfunction "168/USB_OTGID_168") (pintype "bidirectional"))
    )
    (net (code "174") (name "unconnected-(CPU1-172{slash}VC_TRST_N-Pad172)") (class "Default")
      (node (ref "CPU1") (pin "172") (pinfunction "172/VC_TRST_N_172") (pintype "bidirectional"))
    )
    (net (code "175") (name "unconnected-(CPU1-174{slash}VC_TDI-Pad174)") (class "Default")
      (node (ref "CPU1") (pin "174") (pinfunction "174/VC_TDI_174") (pintype "bidirectional"))
    )
    (net (code "176") (name "unconnected-(CPU1-176{slash}VC_TMS-Pad176)") (class "Default")
      (node (ref "CPU1") (pin "176") (pinfunction "176/VC_TMS_176") (pintype "bidirectional"))
    )
    (net (code "177") (name "unconnected-(CPU1-177{slash}RUN-Pad177)") (class "Default")
      (node (ref "CPU1") (pin "177") (pinfunction "177/RUN_177") (pintype "bidirectional"))
    )
    (net (code "178") (name "unconnected-(CPU1-178{slash}VC_TDO-Pad178)") (class "Default")
      (node (ref "CPU1") (pin "178") (pinfunction "178/VC_TDO_178") (pintype "bidirectional"))
    )
    (net (code "179") (name "unconnected-(CPU1-179{slash}VDD_CORE-Pad179)") (class "Default")
      (node (ref "CPU1") (pin "179") (pinfunction "179/VDD_CORE_179") (pintype "bidirectional"))
    )
    (net (code "180") (name "unconnected-(CPU1-180{slash}VC_TCK-Pad180)") (class "Default")
      (node (ref "CPU1") (pin "180") (pinfunction "180/VC_TCK_180") (pintype "bidirectional"))
    )
    (net (code "181") (name "unconnected-(IC1-RPU2-PadB1)") (class "Default")
      (node (ref "IC1") (pin "B1") (pinfunction "RPU2_B1") (pintype "bidirectional"))
    )
    (net (code "182") (name "unconnected-(IC4-NU-Pad7)") (class "Default")
      (node (ref "IC4") (pin "7") (pinfunction "NU_7") (pintype "passive"))
    )
    (net (code "183") (name "unconnected-(IC4-ORG-Pad6)") (class "Default")
      (node (ref "IC4") (pin "6") (pinfunction "ORG_6") (pintype "input"))
    )
    (net (code "184") (name "unconnected-(J3-PadID)") (class "Default")
      (node (ref "J3") (pin "ID") (pinfunction "ID_ID") (pintype "bidirectional"))
    )
    (net (code "185") (name "unconnected-(J5-NC-Pad4)") (class "Default")
      (node (ref "J5") (pin "4") (pinfunction "NC_4") (pintype "bidirectional"))
    )
    (net (code "186") (name "unconnected-(J5-NC-Pad5)") (class "Default")
      (node (ref "J5") (pin "5") (pinfunction "NC_5") (pintype "bidirectional"))
    )
    (net (code "187") (name "unconnected-(J6-DETECT_TERM-PadDET_T)") (class "Default")
      (node (ref "J6") (pin "DET_T") (pinfunction "DETECT_TERM_DET_T") (pintype "passive"))
    )
    (net (code "188") (name "unconnected-(J6-SWITCH_TERM-PadSW_T)") (class "Default")
      (node (ref "J6") (pin "SW_T") (pinfunction "SWITCH_TERM_SW_T") (pintype "passive"))
    )
    (net (code "189") (name "unconnected-(J7-Pad4)") (class "Default")
      (node (ref "J7") (pin "4") (pinfunction "4_4") (pintype "passive"))
    )
    (net (code "190") (name "unconnected-(J7-Pad5)") (class "Default")
      (node (ref "J7") (pin "5") (pinfunction "5_5") (pintype "passive"))
    )
    (net (code "191") (name "unconnected-(J7-Pad8)") (class "Default")
      (node (ref "J7") (pin "8") (pinfunction "8_8") (pintype "passive"))
    )
    (net (code "192") (name "unconnected-(J7-Pad9)") (class "Default")
      (node (ref "J7") (pin "9") (pinfunction "9_9") (pintype "passive"))
    )
    (net (code "193") (name "unconnected-(U$6-UTIL-PadP$14)") (class "Default")
      (node (ref "U$6") (pin "P$14") (pinfunction "UTIL_P$14") (pintype "bidirectional"))
    )
    (net (code "194") (name "unconnected-(U5-CLK24_EN-Pad44)") (class "Default")
      (node (ref "U5") (pin "44") (pinfunction "CLK24_EN_44") (pintype "input"))
    )
    (net (code "195") (name "unconnected-(U5-CLK24_OUT-Pad45)") (class "Default")
      (node (ref "U5") (pin "45") (pinfunction "CLK24_OUT_45") (pintype "output"))
    )
    (net (code "196") (name "unconnected-(U5-GPIO3-Pad35)") (class "Default")
      (node (ref "U5") (pin "35") (pinfunction "GPIO3_35") (pintype "bidirectional"))
    )
    (net (code "197") (name "unconnected-(U5-GPIO4-Pad36)") (class "Default")
      (node (ref "U5") (pin "36") (pinfunction "GPIO4_36") (pintype "bidirectional"))
    )
    (net (code "198") (name "unconnected-(U5-GPIO5-Pad37)") (class "Default")
      (node (ref "U5") (pin "37") (pinfunction "GPIO5_37") (pintype "bidirectional"))
    )
    (net (code "199") (name "unconnected-(U5-GPIO6-Pad42)") (class "Default")
      (node (ref "U5") (pin "42") (pinfunction "GPIO6_42") (pintype "bidirectional"))
    )
    (net (code "200") (name "unconnected-(U5-GPIO7-Pad43)") (class "Default")
      (node (ref "U5") (pin "43") (pinfunction "GPIO7_43") (pintype "bidirectional"))
    )
    (net (code "201") (name "unconnected-(U5-NC-Pad18)") (class "Default")
      (node (ref "U5") (pin "18") (pinfunction "NC_18") (pintype "no_connect"))
    )
    (net (code "202") (name "unconnected-(U5-NC_2-Pad6)") (class "Default")
      (node (ref "U5") (pin "6") (pinfunction "NC_2_6") (pintype "no_connect"))
    )
    (net (code "203") (name "unconnected-(U5-NC_3-Pad7)") (class "Default")
      (node (ref "U5") (pin "7") (pinfunction "NC_3_7") (pintype "no_connect"))
    )
    (net (code "204") (name "unconnected-(U5-NC_4-Pad8)") (class "Default")
      (node (ref "U5") (pin "8") (pinfunction "NC_4_8") (pintype "no_connect"))
    )
    (net (code "205") (name "unconnected-(U5-NC_5-Pad9)") (class "Default")
      (node (ref "U5") (pin "9") (pinfunction "NC_5_9") (pintype "no_connect"))
    )
    (net (code "206") (name "unconnected-(U5-NC_6-Pad17)") (class "Default")
      (node (ref "U5") (pin "17") (pinfunction "NC_6_17") (pintype "no_connect"))
    )
    (net (code "207") (name "unconnected-(U5-NTRST-Pad28)") (class "Default")
      (node (ref "U5") (pin "28") (pinfunction "NTRST_28") (pintype "input"))
    )
    (net (code "208") (name "unconnected-(U5-TCK-Pad32)") (class "Default")
      (node (ref "U5") (pin "32") (pinfunction "TCK_32") (pintype "input"))
    )
    (net (code "209") (name "unconnected-(U5-TDI-Pad30)") (class "Default")
      (node (ref "U5") (pin "30") (pinfunction "TDI_30") (pintype "input"))
    )
    (net (code "210") (name "unconnected-(U5-TDO-Pad31)") (class "Default")
      (node (ref "U5") (pin "31") (pinfunction "TDO_31") (pintype "output"))
    )
    (net (code "211") (name "unconnected-(U5-TEST1-Pad13)") (class "Default")
      (node (ref "U5") (pin "13") (pinfunction "TEST1_13") (pintype "passive"))
    )
    (net (code "212") (name "unconnected-(U5-TEST4-Pad47)") (class "Default")
      (node (ref "U5") (pin "47") (pinfunction "TEST4_47") (pintype "passive"))
    )
    (net (code "213") (name "unconnected-(U5-TMS-Pad29)") (class "Default")
      (node (ref "U5") (pin "29") (pinfunction "TMS_29") (pintype "input"))
    )
    (net (code "214") (name "unconnected-(U6-~{OE}-Pad8)") (class "Default")
      (node (ref "U6") (pin "8") (pinfunction "~{OE}_8") (pintype "input"))
    )
  )
)
